# prototype_board.net
KiCad netlist of a schematic drawn in EAGLE
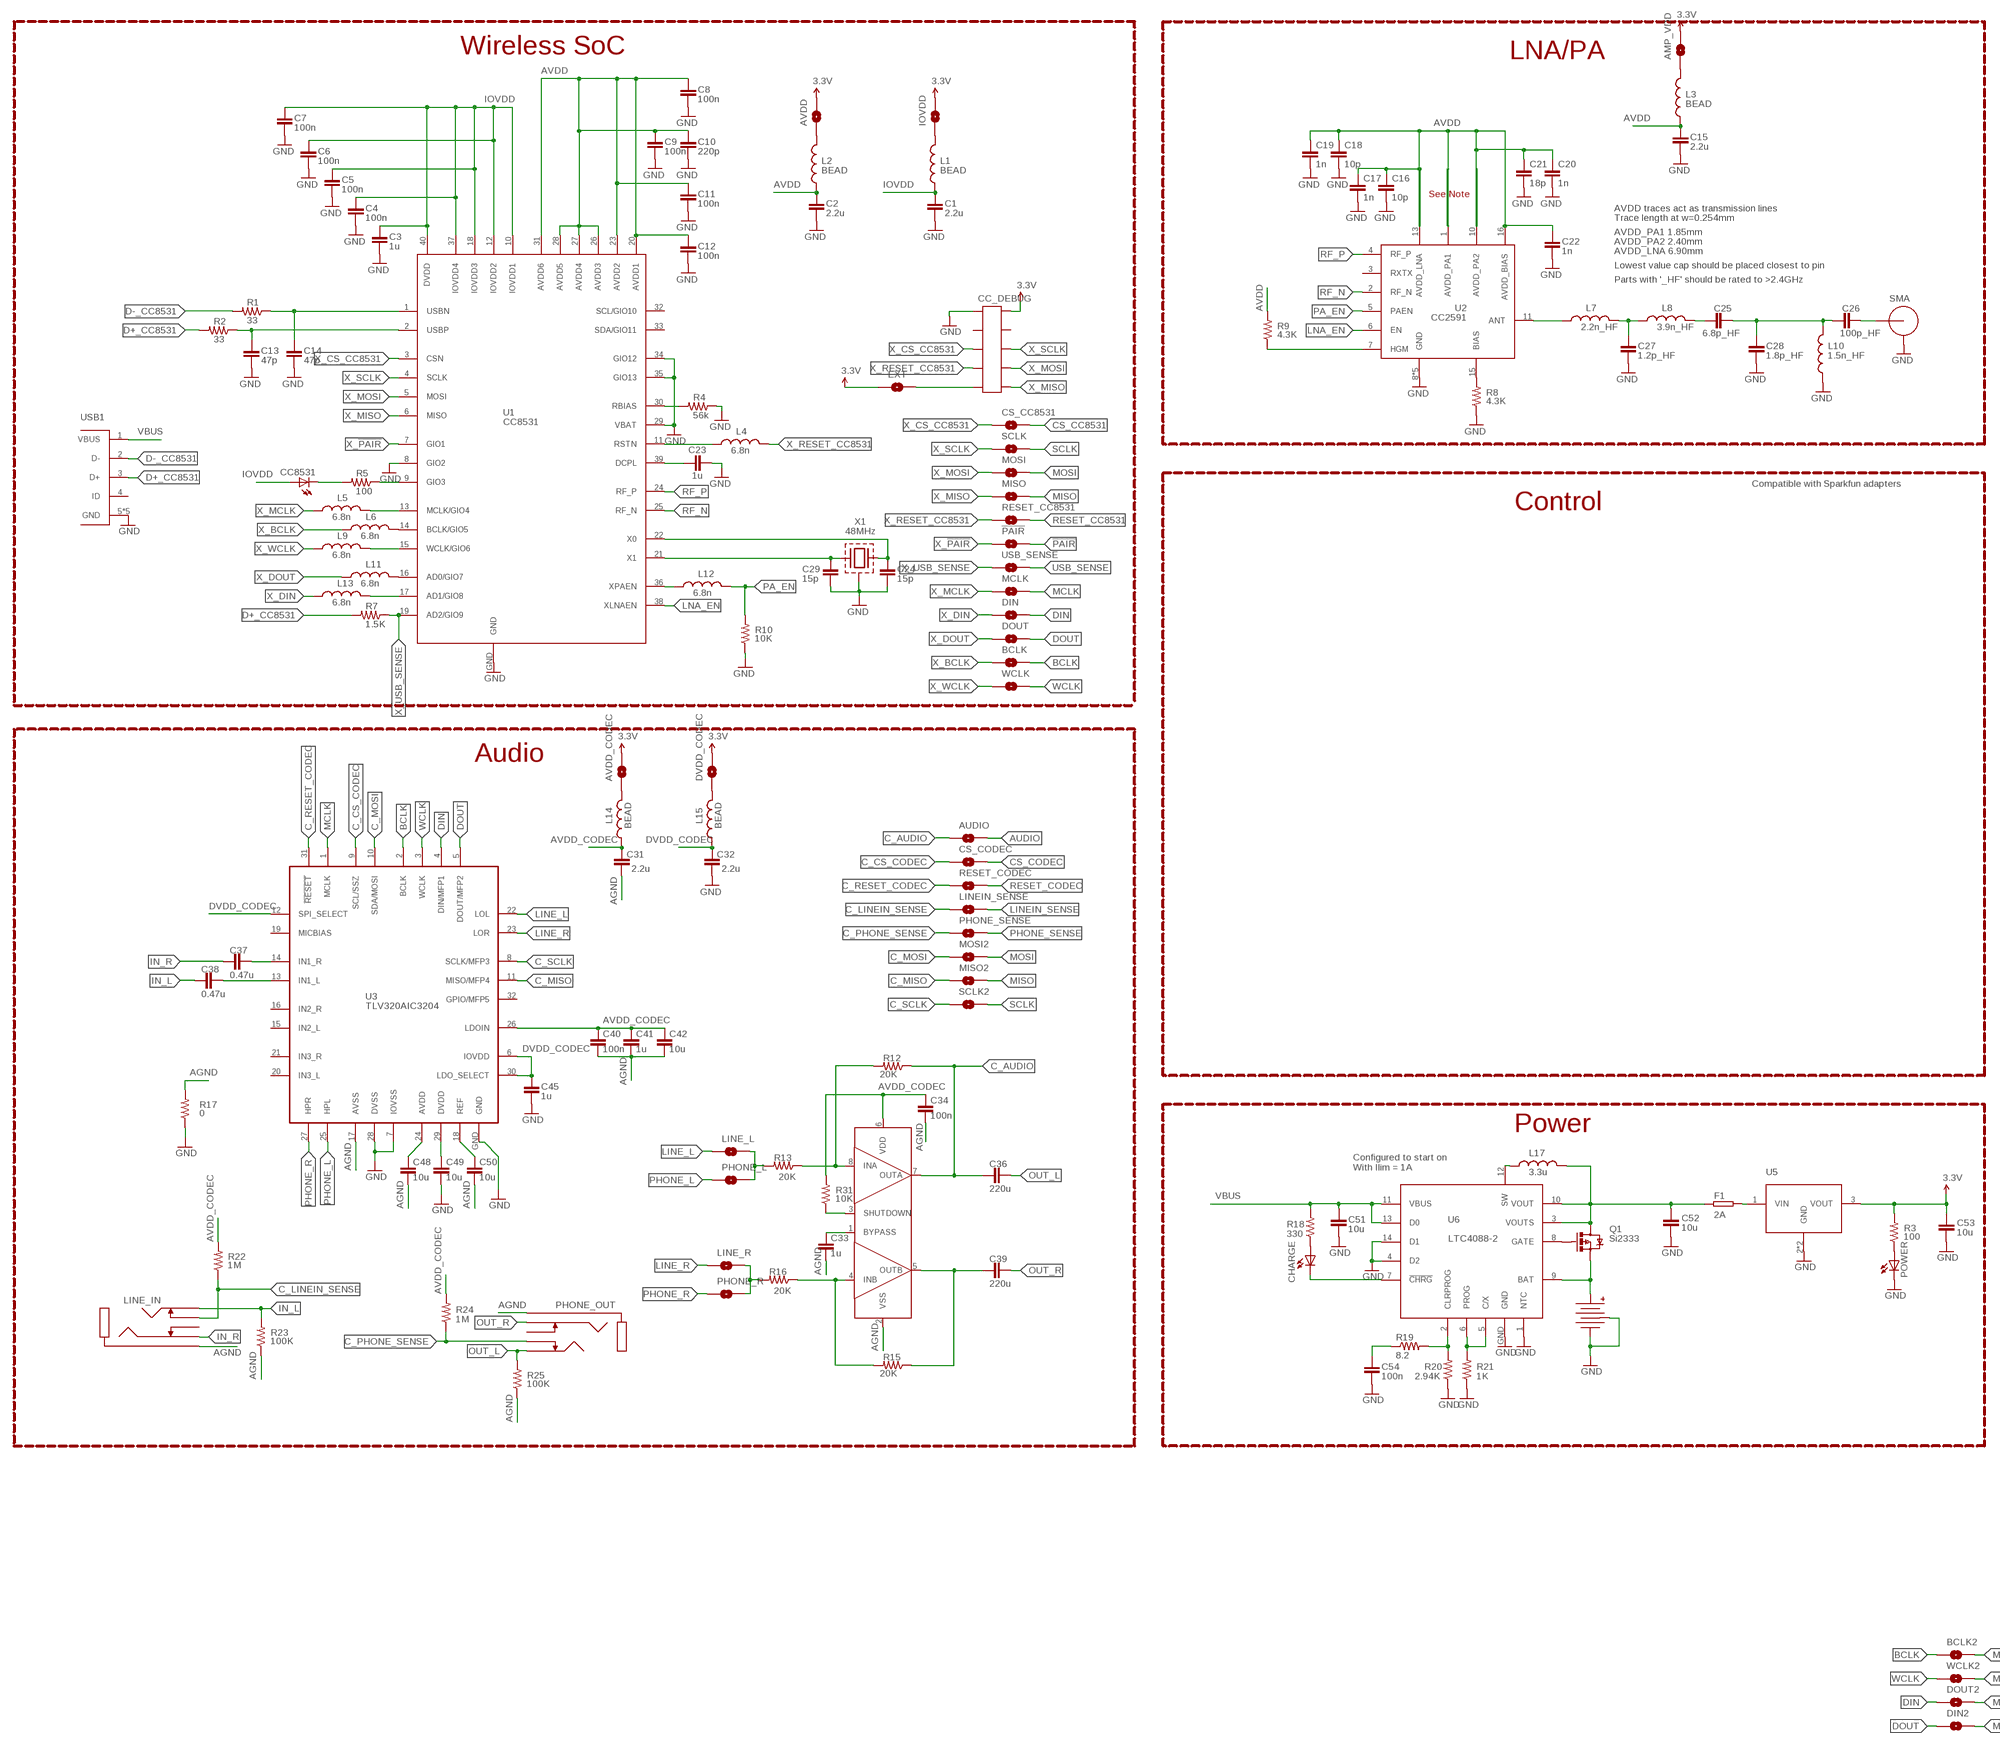
[diagram p0: schematic, sheet 1, part 1 of 3]
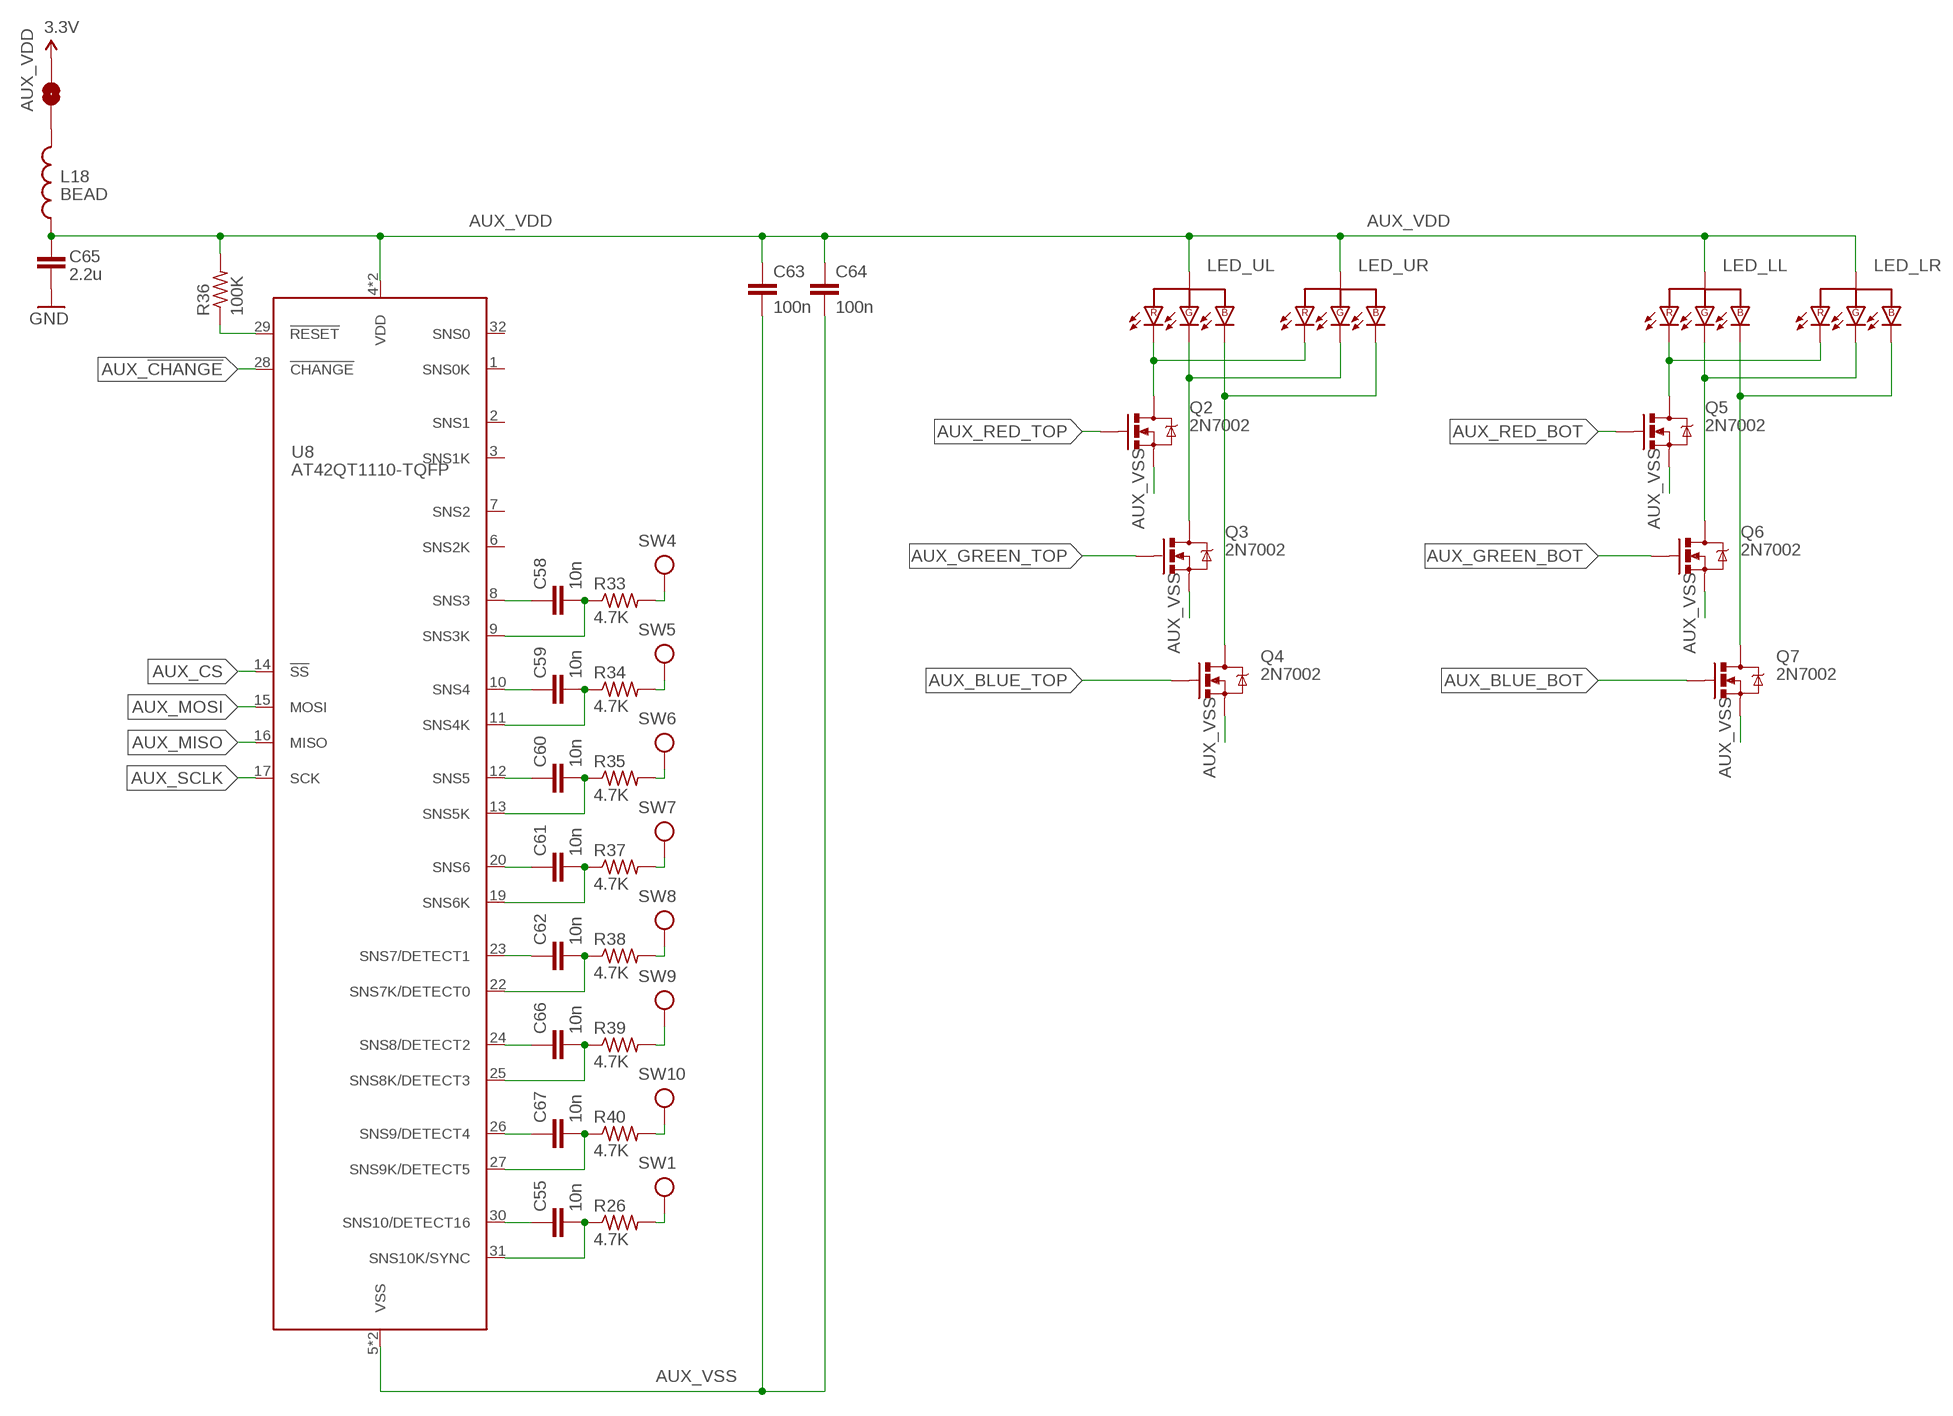
[diagram p1: schematic, sheet 1, part 2 of 3]
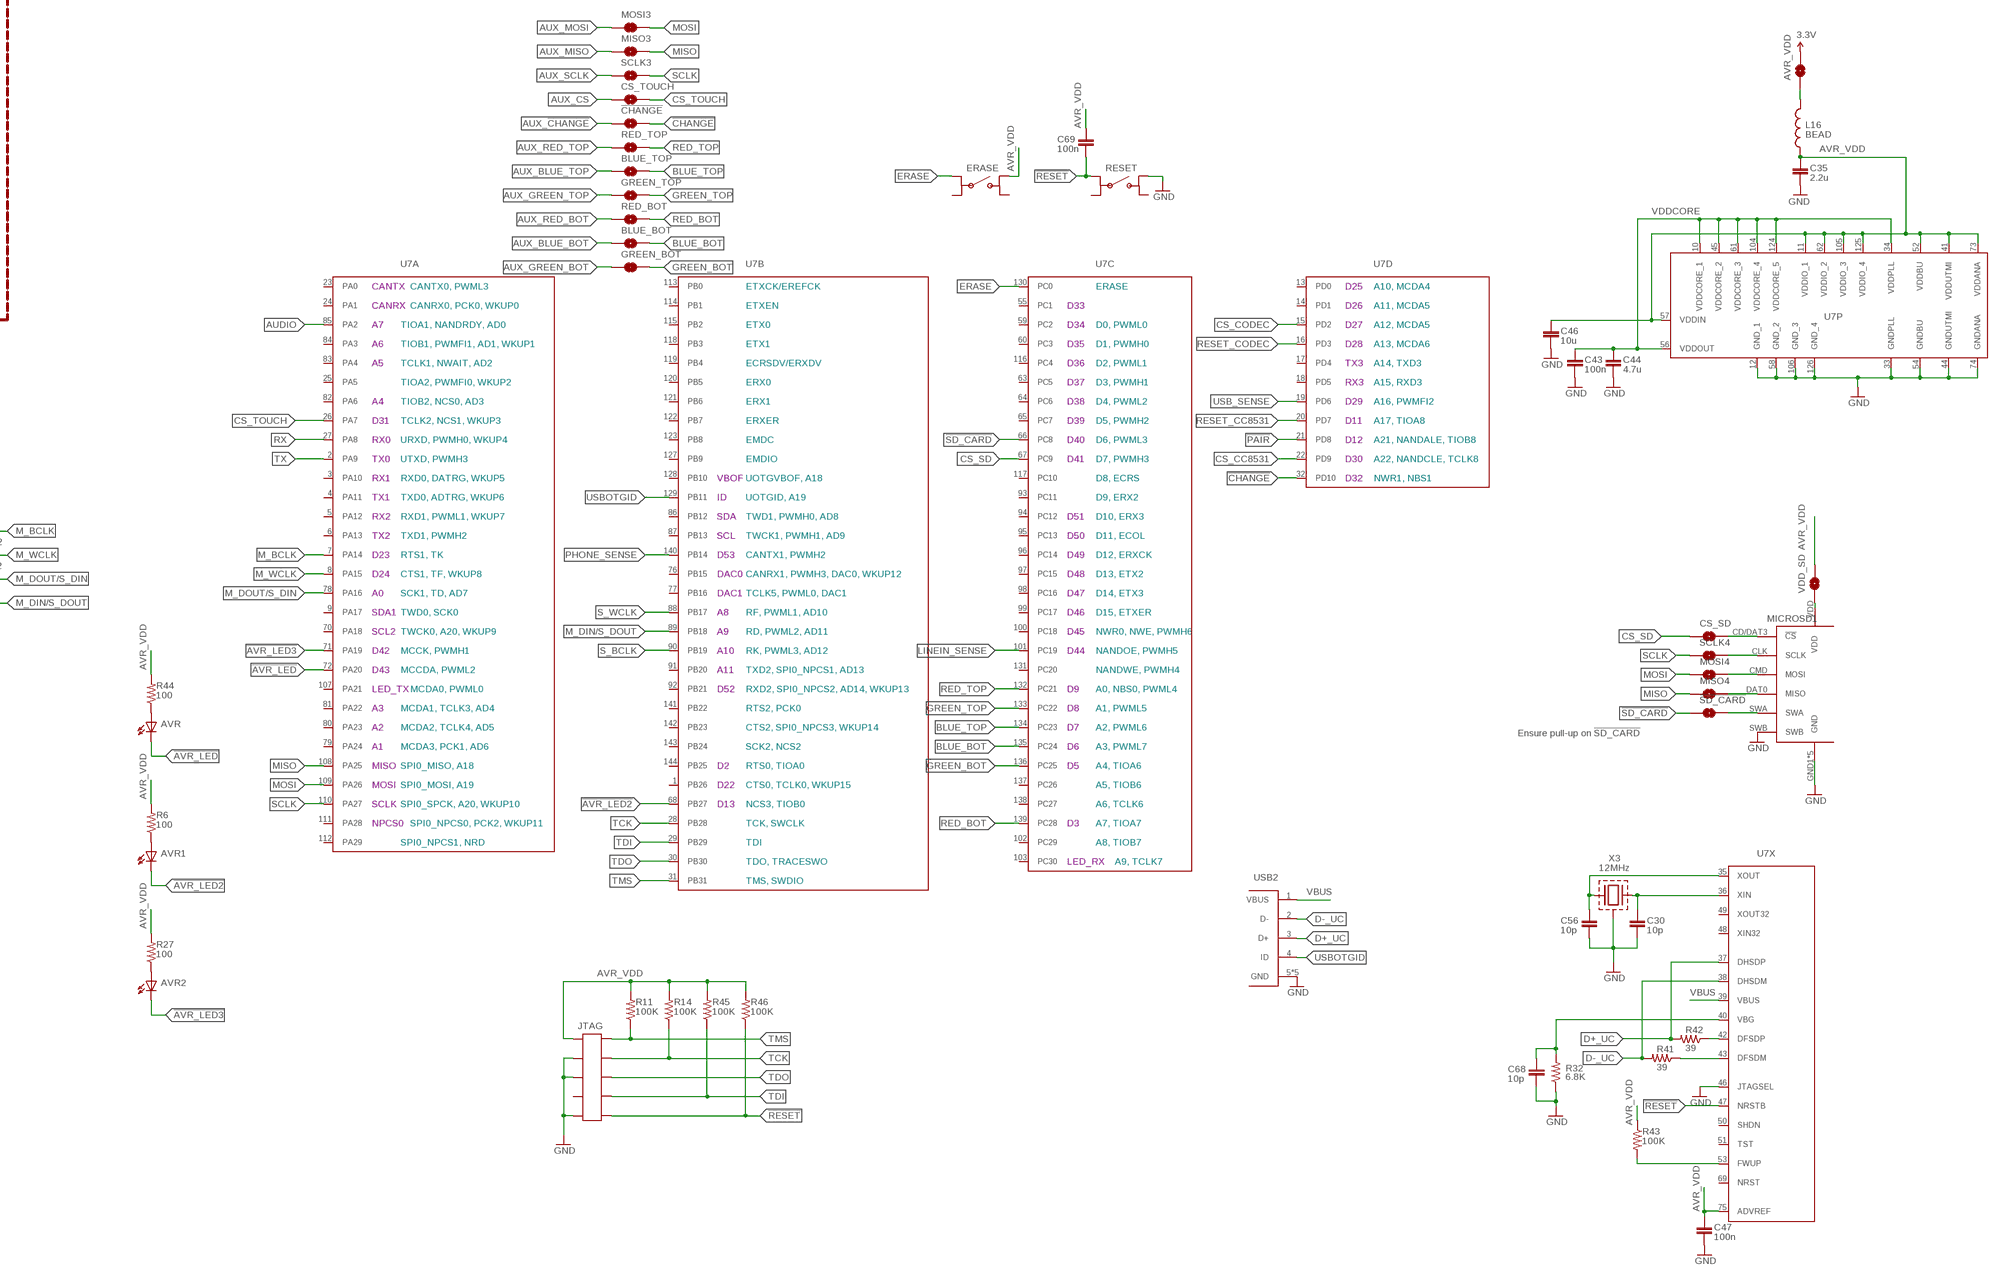
[diagram p2: schematic, sheet 1, part 3 of 3]

(export (version "E")
  (design (tool "Eeschema 10.0.6"))
  (components
    (comp (ref "!CHANGE")
      (value "SOLDERJUMPERNO")
      (footprint "eagle-import:SJ_2S-NO")
      (libsource (lib "eagle-import") (part "SOLDERJUMPERNO"))
    )
    (comp (ref "!PAIR")
      (value "SOLDERJUMPERNO")
      (footprint "eagle-import:SJ_2S-NO")
      (libsource (lib "eagle-import") (part "SOLDERJUMPERNO"))
    )
    (comp (ref "!SD_CARD")
      (value "SOLDERJUMPERNO")
      (footprint "eagle-import:SJ_2S-NO")
      (libsource (lib "eagle-import") (part "SOLDERJUMPERNO"))
    )
    (comp (ref "AMP_VDD")
      (value "SOLDERJUMPERNO")
      (footprint "eagle-import:SJ_2S-NO")
      (libsource (lib "eagle-import") (part "SOLDERJUMPERNO"))
    )
    (comp (ref "AUDIO")
      (value "SOLDERJUMPERNO")
      (footprint "eagle-import:SJ_2S-NO")
      (libsource (lib "eagle-import") (part "SOLDERJUMPERNO"))
    )
    (comp (ref "AUX_VDD")
      (value "SOLDERJUMPERNO")
      (footprint "eagle-import:SJ_2S-NO")
      (libsource (lib "eagle-import") (part "SOLDERJUMPERNO"))
    )
    (comp (ref "AVDD")
      (value "SOLDERJUMPERNO")
      (footprint "eagle-import:SJ_2S-NO")
      (libsource (lib "eagle-import") (part "SOLDERJUMPERNO"))
    )
    (comp (ref "AVDD_CODEC")
      (value "SOLDERJUMPERNO")
      (footprint "eagle-import:SJ_2S-NO")
      (libsource (lib "eagle-import") (part "SOLDERJUMPERNO"))
    )
    (comp (ref "AVR")
      (value "LED1206")
      (footprint "eagle-import:LED-1206")
      (libsource (lib "eagle-import") (part "LED1206"))
    )
    (comp (ref "AVR1")
      (value "LED1206")
      (footprint "eagle-import:LED-1206")
      (libsource (lib "eagle-import") (part "LED1206"))
    )
    (comp (ref "AVR2")
      (value "LED1206")
      (footprint "eagle-import:LED-1206")
      (libsource (lib "eagle-import") (part "LED1206"))
    )
    (comp (ref "AVR_VDD")
      (value "SOLDERJUMPERNO")
      (footprint "eagle-import:SJ_2S-NO")
      (libsource (lib "eagle-import") (part "SOLDERJUMPERNO"))
    )
    (comp (ref "BATTERY")
      (value "BATTERY-LIPO-JST")
      (footprint "eagle-import:1775469-2")
      (libsource (lib "eagle-import") (part "BATTERY-LIPO-JST"))
    )
    (comp (ref "BCLK")
      (value "SOLDERJUMPERNO")
      (footprint "eagle-import:SJ_2S-NO")
      (libsource (lib "eagle-import") (part "SOLDERJUMPERNO"))
    )
    (comp (ref "BCLK2")
      (value "SOLDERJUMPERNO")
      (footprint "eagle-import:SJ_2S-NO")
      (libsource (lib "eagle-import") (part "SOLDERJUMPERNO"))
    )
    (comp (ref "BLUE_BOT")
      (value "SOLDERJUMPERNO")
      (footprint "eagle-import:SJ_2S-NO")
      (libsource (lib "eagle-import") (part "SOLDERJUMPERNO"))
    )
    (comp (ref "BLUE_TOP")
      (value "SOLDERJUMPERNO")
      (footprint "eagle-import:SJ_2S-NO")
      (libsource (lib "eagle-import") (part "SOLDERJUMPERNO"))
    )
    (comp (ref "C1")
      (value "2.2u")
      (footprint "eagle-import:C0603")
      (libsource (lib "eagle-import") (part "rcl_C-EUC0603"))
    )
    (comp (ref "C2")
      (value "2.2u")
      (footprint "eagle-import:C0603")
      (libsource (lib "eagle-import") (part "rcl_C-EUC0603"))
    )
    (comp (ref "C3")
      (value "1u")
      (footprint "eagle-import:C0603")
      (libsource (lib "eagle-import") (part "rcl_C-EUC0603"))
    )
    (comp (ref "C4")
      (value "100n")
      (footprint "eagle-import:C0603")
      (libsource (lib "eagle-import") (part "rcl_C-EUC0603"))
    )
    (comp (ref "C5")
      (value "100n")
      (footprint "eagle-import:C0603")
      (libsource (lib "eagle-import") (part "rcl_C-EUC0603"))
    )
    (comp (ref "C6")
      (value "100n")
      (footprint "eagle-import:C0603")
      (libsource (lib "eagle-import") (part "rcl_C-EUC0603"))
    )
    (comp (ref "C7")
      (value "100n")
      (footprint "eagle-import:C0603")
      (libsource (lib "eagle-import") (part "rcl_C-EUC0603"))
    )
    (comp (ref "C8")
      (value "100n")
      (footprint "eagle-import:C0603")
      (libsource (lib "eagle-import") (part "rcl_C-EUC0603"))
    )
    (comp (ref "C9")
      (value "100n")
      (footprint "eagle-import:C0603")
      (libsource (lib "eagle-import") (part "rcl_C-EUC0603"))
    )
    (comp (ref "C10")
      (value "220p")
      (footprint "eagle-import:C0603")
      (libsource (lib "eagle-import") (part "rcl_C-EUC0603"))
    )
    (comp (ref "C11")
      (value "100n")
      (footprint "eagle-import:C0603")
      (libsource (lib "eagle-import") (part "rcl_C-EUC0603"))
    )
    (comp (ref "C12")
      (value "100n")
      (footprint "eagle-import:C0603")
      (libsource (lib "eagle-import") (part "rcl_C-EUC0603"))
    )
    (comp (ref "C13")
      (value "47p")
      (footprint "eagle-import:C0603")
      (libsource (lib "eagle-import") (part "rcl_C-EUC0603"))
    )
    (comp (ref "C14")
      (value "47p")
      (footprint "eagle-import:C0603")
      (libsource (lib "eagle-import") (part "rcl_C-EUC0603"))
    )
    (comp (ref "C15")
      (value "2.2u")
      (footprint "eagle-import:C0603")
      (libsource (lib "eagle-import") (part "rcl_C-EUC0603"))
    )
    (comp (ref "C16")
      (value "10p")
      (footprint "eagle-import:C0603")
      (libsource (lib "eagle-import") (part "rcl_C-EUC0603"))
    )
    (comp (ref "C17")
      (value "1n")
      (footprint "eagle-import:C0603")
      (libsource (lib "eagle-import") (part "rcl_C-EUC0603"))
    )
    (comp (ref "C18")
      (value "10p")
      (footprint "eagle-import:C0603")
      (libsource (lib "eagle-import") (part "rcl_C-EUC0603"))
    )
    (comp (ref "C19")
      (value "1n")
      (footprint "eagle-import:C0603")
      (libsource (lib "eagle-import") (part "rcl_C-EUC0603"))
    )
    (comp (ref "C20")
      (value "1n")
      (footprint "eagle-import:C0603")
      (libsource (lib "eagle-import") (part "rcl_C-EUC0603"))
    )
    (comp (ref "C21")
      (value "18p")
      (footprint "eagle-import:C0603")
      (libsource (lib "eagle-import") (part "rcl_C-EUC0603"))
    )
    (comp (ref "C22")
      (value "1n")
      (footprint "eagle-import:C0603")
      (libsource (lib "eagle-import") (part "rcl_C-EUC0603"))
    )
    (comp (ref "C23")
      (value "1u")
      (footprint "eagle-import:C0603")
      (libsource (lib "eagle-import") (part "rcl_C-EUC0603"))
    )
    (comp (ref "C24")
      (value "15p")
      (footprint "eagle-import:C0603")
      (libsource (lib "eagle-import") (part "rcl_C-EUC0603"))
    )
    (comp (ref "C25")
      (value "6.8p_HF")
      (footprint "eagle-import:C0603")
      (libsource (lib "eagle-import") (part "rcl_C-EUC0603"))
    )
    (comp (ref "C26")
      (value "100p_HF")
      (footprint "eagle-import:C0603")
      (libsource (lib "eagle-import") (part "rcl_C-EUC0603"))
    )
    (comp (ref "C27")
      (value "1.2p_HF")
      (footprint "eagle-import:C0603")
      (libsource (lib "eagle-import") (part "rcl_C-EUC0603"))
    )
    (comp (ref "C28")
      (value "1.8p_HF")
      (footprint "eagle-import:C0603")
      (libsource (lib "eagle-import") (part "rcl_C-EUC0603"))
    )
    (comp (ref "C29")
      (value "15p")
      (footprint "eagle-import:C0603")
      (libsource (lib "eagle-import") (part "rcl_C-EUC0603"))
    )
    (comp (ref "C30")
      (value "10p")
      (footprint "eagle-import:C0603")
      (libsource (lib "eagle-import") (part "C-EUC0603"))
    )
    (comp (ref "C31")
      (value "2.2u")
      (footprint "eagle-import:C0603")
      (libsource (lib "eagle-import") (part "rcl_C-EUC0603"))
    )
    (comp (ref "C32")
      (value "2.2u")
      (footprint "eagle-import:C0603")
      (libsource (lib "eagle-import") (part "rcl_C-EUC0603"))
    )
    (comp (ref "C33")
      (value "1u")
      (footprint "eagle-import:C0603")
      (libsource (lib "eagle-import") (part "rcl_C-EUC0603"))
    )
    (comp (ref "C34")
      (value "100n")
      (footprint "eagle-import:C0603")
      (libsource (lib "eagle-import") (part "rcl_C-EUC0603"))
    )
    (comp (ref "C35")
      (value "2.2u")
      (footprint "eagle-import:C0603")
      (libsource (lib "eagle-import") (part "rcl_C-EUC0603"))
    )
    (comp (ref "C36")
      (value "220u")
      (footprint "eagle-import:C1210")
      (libsource (lib "eagle-import") (part "C-EUC1210"))
    )
    (comp (ref "C37")
      (value "0.47u")
      (footprint "eagle-import:C0603")
      (libsource (lib "eagle-import") (part "rcl_C-EUC0603"))
    )
    (comp (ref "C38")
      (value "0.47u")
      (footprint "eagle-import:C0603")
      (libsource (lib "eagle-import") (part "rcl_C-EUC0603"))
    )
    (comp (ref "C39")
      (value "220u")
      (footprint "eagle-import:C1210")
      (libsource (lib "eagle-import") (part "C-EUC1210"))
    )
    (comp (ref "C40")
      (value "100n")
      (footprint "eagle-import:C0603")
      (libsource (lib "eagle-import") (part "rcl_C-EUC0603"))
    )
    (comp (ref "C41")
      (value "1u")
      (footprint "eagle-import:C0603")
      (libsource (lib "eagle-import") (part "rcl_C-EUC0603"))
    )
    (comp (ref "C42")
      (value "10u")
      (footprint "eagle-import:C0603")
      (libsource (lib "eagle-import") (part "rcl_C-EUC0603"))
    )
    (comp (ref "C43")
      (value "100n")
      (footprint "eagle-import:C0603")
      (libsource (lib "eagle-import") (part "rcl_C-EUC0603"))
    )
    (comp (ref "C44")
      (value "4.7u")
      (footprint "eagle-import:C0603")
      (libsource (lib "eagle-import") (part "rcl_C-EUC0603"))
    )
    (comp (ref "C45")
      (value "1u")
      (footprint "eagle-import:C0603")
      (libsource (lib "eagle-import") (part "rcl_C-EUC0603"))
    )
    (comp (ref "C46")
      (value "10u")
      (footprint "eagle-import:C0603")
      (libsource (lib "eagle-import") (part "rcl_C-EUC0603"))
    )
    (comp (ref "C47")
      (value "100n")
      (footprint "eagle-import:C0603")
      (libsource (lib "eagle-import") (part "rcl_C-EUC0603"))
    )
    (comp (ref "C48")
      (value "10u")
      (footprint "eagle-import:C0603")
      (libsource (lib "eagle-import") (part "rcl_C-EUC0603"))
    )
    (comp (ref "C49")
      (value "10u")
      (footprint "eagle-import:C0603")
      (libsource (lib "eagle-import") (part "rcl_C-EUC0603"))
    )
    (comp (ref "C50")
      (value "10u")
      (footprint "eagle-import:C0603")
      (libsource (lib "eagle-import") (part "rcl_C-EUC0603"))
    )
    (comp (ref "C51")
      (value "10u")
      (footprint "eagle-import:C0603")
      (libsource (lib "eagle-import") (part "C-EUC0603"))
    )
    (comp (ref "C52")
      (value "10u")
      (footprint "eagle-import:C0603")
      (libsource (lib "eagle-import") (part "rcl_C-EUC0603"))
    )
    (comp (ref "C53")
      (value "10u")
      (footprint "eagle-import:C0603")
      (libsource (lib "eagle-import") (part "rcl_C-EUC0603"))
    )
    (comp (ref "C54")
      (value "100n")
      (footprint "eagle-import:C0603")
      (libsource (lib "eagle-import") (part "C-EUC0603"))
    )
    (comp (ref "C55")
      (value "10n")
      (footprint "eagle-import:C0603")
      (libsource (lib "eagle-import") (part "rcl_C-EUC0603"))
    )
    (comp (ref "C56")
      (value "10p")
      (footprint "eagle-import:C0603")
      (libsource (lib "eagle-import") (part "C-EUC0603"))
    )
    (comp (ref "C58")
      (value "10n")
      (footprint "eagle-import:C0603")
      (libsource (lib "eagle-import") (part "rcl_C-EUC0603"))
    )
    (comp (ref "C59")
      (value "10n")
      (footprint "eagle-import:C0603")
      (libsource (lib "eagle-import") (part "rcl_C-EUC0603"))
    )
    (comp (ref "C60")
      (value "10n")
      (footprint "eagle-import:C0603")
      (libsource (lib "eagle-import") (part "rcl_C-EUC0603"))
    )
    (comp (ref "C61")
      (value "10n")
      (footprint "eagle-import:C0603")
      (libsource (lib "eagle-import") (part "rcl_C-EUC0603"))
    )
    (comp (ref "C62")
      (value "10n")
      (footprint "eagle-import:C0603")
      (libsource (lib "eagle-import") (part "rcl_C-EUC0603"))
    )
    (comp (ref "C63")
      (value "100n")
      (footprint "eagle-import:C0603")
      (libsource (lib "eagle-import") (part "rcl_C-EUC0603"))
    )
    (comp (ref "C64")
      (value "100n")
      (footprint "eagle-import:C0603")
      (libsource (lib "eagle-import") (part "rcl_C-EUC0603"))
    )
    (comp (ref "C65")
      (value "2.2u")
      (footprint "eagle-import:C0603")
      (libsource (lib "eagle-import") (part "rcl_C-EUC0603"))
    )
    (comp (ref "C66")
      (value "10n")
      (footprint "eagle-import:C0603")
      (libsource (lib "eagle-import") (part "rcl_C-EUC0603"))
    )
    (comp (ref "C67")
      (value "10n")
      (footprint "eagle-import:C0603")
      (libsource (lib "eagle-import") (part "rcl_C-EUC0603"))
    )
    (comp (ref "C68")
      (value "10p")
      (footprint "eagle-import:C0603")
      (libsource (lib "eagle-import") (part "C-EUC0603"))
    )
    (comp (ref "C69")
      (value "100n")
      (footprint "eagle-import:C0603")
      (libsource (lib "eagle-import") (part "C-EUC0603"))
    )
    (comp (ref "CC8531")
      (value "LED1206")
      (footprint "eagle-import:LED-1206")
      (libsource (lib "eagle-import") (part "LED1206"))
    )
    (comp (ref "CC_DEBUG")
      (value "HEADER-10P-SMD-MALE2")
      (footprint "eagle-import:HEADER-10P-1.27MM")
      (libsource (lib "eagle-import") (part "HEADER-10P-SMD-MALE2"))
    )
    (comp (ref "CHARGE")
      (value "LED1206")
      (footprint "eagle-import:LED-1206")
      (libsource (lib "eagle-import") (part "LED1206"))
    )
    (comp (ref "CS_CC8531")
      (value "SOLDERJUMPERNO")
      (footprint "eagle-import:SJ_2S-NO")
      (libsource (lib "eagle-import") (part "SOLDERJUMPERNO"))
    )
    (comp (ref "CS_CODEC")
      (value "SOLDERJUMPERNO")
      (footprint "eagle-import:SJ_2S-NO")
      (libsource (lib "eagle-import") (part "SOLDERJUMPERNO"))
    )
    (comp (ref "CS_SD")
      (value "SOLDERJUMPERNO")
      (footprint "eagle-import:SJ_2S-NO")
      (libsource (lib "eagle-import") (part "SOLDERJUMPERNO"))
    )
    (comp (ref "CS_TOUCH")
      (value "SOLDERJUMPERNO")
      (footprint "eagle-import:SJ_2S-NO")
      (libsource (lib "eagle-import") (part "SOLDERJUMPERNO"))
    )
    (comp (ref "DIN")
      (value "SOLDERJUMPERNO")
      (footprint "eagle-import:SJ_2S-NO")
      (libsource (lib "eagle-import") (part "SOLDERJUMPERNO"))
    )
    (comp (ref "DIN2")
      (value "SOLDERJUMPERNO")
      (footprint "eagle-import:SJ_2S-NO")
      (libsource (lib "eagle-import") (part "SOLDERJUMPERNO"))
    )
    (comp (ref "DOUT")
      (value "SOLDERJUMPERNO")
      (footprint "eagle-import:SJ_2S-NO")
      (libsource (lib "eagle-import") (part "SOLDERJUMPERNO"))
    )
    (comp (ref "DOUT2")
      (value "SOLDERJUMPERNO")
      (footprint "eagle-import:SJ_2S-NO")
      (libsource (lib "eagle-import") (part "SOLDERJUMPERNO"))
    )
    (comp (ref "DVDD_CODEC")
      (value "SOLDERJUMPERNO")
      (footprint "eagle-import:SJ_2S-NO")
      (libsource (lib "eagle-import") (part "SOLDERJUMPERNO"))
    )
    (comp (ref "ERASE")
      (value "TACT_SWITCH-PTS-525")
      (footprint "eagle-import:PTS-525")
      (libsource (lib "eagle-import") (part "TACT_SWITCH-PTS-525"))
    )
    (comp (ref "EXT")
      (value "SOLDERJUMPERNO")
      (footprint "eagle-import:SJ_2S-NO")
      (libsource (lib "eagle-import") (part "SOLDERJUMPERNO"))
    )
    (comp (ref "F1")
      (value "2A")
      (footprint "eagle-import:1210")
      (libsource (lib "eagle-import") (part "PTC_FUSE"))
    )
    (comp (ref "GREEN_BOT")
      (value "SOLDERJUMPERNO")
      (footprint "eagle-import:SJ_2S-NO")
      (libsource (lib "eagle-import") (part "SOLDERJUMPERNO"))
    )
    (comp (ref "GREEN_TOP")
      (value "SOLDERJUMPERNO")
      (footprint "eagle-import:SJ_2S-NO")
      (libsource (lib "eagle-import") (part "SOLDERJUMPERNO"))
    )
    (comp (ref "IOVDD")
      (value "SOLDERJUMPERNO")
      (footprint "eagle-import:SJ_2S-NO")
      (libsource (lib "eagle-import") (part "SOLDERJUMPERNO"))
    )
    (comp (ref "JTAG")
      (value "HEADER-10P-SMD-MALE2")
      (footprint "eagle-import:HEADER-10P-1.27MM")
      (libsource (lib "eagle-import") (part "HEADER-10P-SMD-MALE2"))
    )
    (comp (ref "L1")
      (value "BEAD")
      (footprint "eagle-import:0603")
      (libsource (lib "eagle-import") (part "INDUCTOR0603"))
    )
    (comp (ref "L2")
      (value "BEAD")
      (footprint "eagle-import:0603")
      (libsource (lib "eagle-import") (part "INDUCTOR0603"))
    )
    (comp (ref "L3")
      (value "BEAD")
      (footprint "eagle-import:0603")
      (libsource (lib "eagle-import") (part "INDUCTOR0603"))
    )
    (comp (ref "L4")
      (value "6.8n")
      (footprint "eagle-import:0603")
      (libsource (lib "eagle-import") (part "INDUCTOR0603"))
    )
    (comp (ref "L5")
      (value "6.8n")
      (footprint "eagle-import:0603")
      (libsource (lib "eagle-import") (part "INDUCTOR0603"))
    )
    (comp (ref "L6")
      (value "6.8n")
      (footprint "eagle-import:0603")
      (libsource (lib "eagle-import") (part "INDUCTOR0603"))
    )
    (comp (ref "L7")
      (value "2.2n_HF")
      (footprint "eagle-import:0603")
      (libsource (lib "eagle-import") (part "INDUCTOR0603"))
    )
    (comp (ref "L8")
      (value "3.9n_HF")
      (footprint "eagle-import:0603")
      (libsource (lib "eagle-import") (part "INDUCTOR0603"))
    )
    (comp (ref "L9")
      (value "6.8n")
      (footprint "eagle-import:0603")
      (libsource (lib "eagle-import") (part "INDUCTOR0603"))
    )
    (comp (ref "L10")
      (value "1.5n_HF")
      (footprint "eagle-import:0603")
      (libsource (lib "eagle-import") (part "INDUCTOR0603"))
    )
    (comp (ref "L11")
      (value "6.8n")
      (footprint "eagle-import:0603")
      (libsource (lib "eagle-import") (part "INDUCTOR0603"))
    )
    (comp (ref "L12")
      (value "6.8n")
      (footprint "eagle-import:0603")
      (libsource (lib "eagle-import") (part "INDUCTOR0603"))
    )
    (comp (ref "L13")
      (value "6.8n")
      (footprint "eagle-import:0603")
      (libsource (lib "eagle-import") (part "INDUCTOR0603"))
    )
    (comp (ref "L14")
      (value "BEAD")
      (footprint "eagle-import:0603")
      (libsource (lib "eagle-import") (part "INDUCTOR0603"))
    )
    (comp (ref "L15")
      (value "BEAD")
      (footprint "eagle-import:0603")
      (libsource (lib "eagle-import") (part "INDUCTOR0603"))
    )
    (comp (ref "L16")
      (value "BEAD")
      (footprint "eagle-import:0603")
      (libsource (lib "eagle-import") (part "INDUCTOR0603"))
    )
    (comp (ref "L17")
      (value "3.3u")
      (footprint "eagle-import:IFSC-1111AB-01")
      (libsource (lib "eagle-import") (part "IFSC-1111AB-01"))
    )
    (comp (ref "L18")
      (value "BEAD")
      (footprint "eagle-import:0603")
      (libsource (lib "eagle-import") (part "INDUCTOR0603"))
    )
    (comp (ref "LED_LL")
      (value "LED_RGB")
      (footprint "eagle-import:PLCC-4")
      (libsource (lib "eagle-import") (part "LED_RGB"))
    )
    (comp (ref "LED_LR")
      (value "LED_RGB")
      (footprint "eagle-import:PLCC-4")
      (libsource (lib "eagle-import") (part "LED_RGB"))
    )
    (comp (ref "LED_UL")
      (value "LED_RGB")
      (footprint "eagle-import:PLCC-4")
      (libsource (lib "eagle-import") (part "LED_RGB"))
    )
    (comp (ref "LED_UR")
      (value "LED_RGB")
      (footprint "eagle-import:PLCC-4")
      (libsource (lib "eagle-import") (part "LED_RGB"))
    )
    (comp (ref "LINEIN_SENSE")
      (value "SOLDERJUMPERNO")
      (footprint "eagle-import:SJ_2S-NO")
      (libsource (lib "eagle-import") (part "SOLDERJUMPERNO"))
    )
    (comp (ref "LINE_IN")
      (value "PHONE_SW-STX-35332-5N")
      (footprint "eagle-import:STX-35332-5N")
      (libsource (lib "eagle-import") (part "PHONE_SW-STX-35332-5N"))
    )
    (comp (ref "LINE_L")
      (value "SOLDERJUMPERNO")
      (footprint "eagle-import:SJ_2S-NO")
      (libsource (lib "eagle-import") (part "SOLDERJUMPERNO"))
    )
    (comp (ref "LINE_R")
      (value "SOLDERJUMPERNO")
      (footprint "eagle-import:SJ_2S-NO")
      (libsource (lib "eagle-import") (part "SOLDERJUMPERNO"))
    )
    (comp (ref "MCLK")
      (value "SOLDERJUMPERNO")
      (footprint "eagle-import:SJ_2S-NO")
      (libsource (lib "eagle-import") (part "SOLDERJUMPERNO"))
    )
    (comp (ref "MICROSD1")
      (value "MICROSD104031-0811")
      (footprint "eagle-import:MOLEX_104031-0811")
      (libsource (lib "eagle-import") (part "MICROSD104031-0811"))
    )
    (comp (ref "MISO")
      (value "SOLDERJUMPERNO")
      (footprint "eagle-import:SJ_2S-NO")
      (libsource (lib "eagle-import") (part "SOLDERJUMPERNO"))
    )
    (comp (ref "MISO2")
      (value "SOLDERJUMPERNO")
      (footprint "eagle-import:SJ_2S-NO")
      (libsource (lib "eagle-import") (part "SOLDERJUMPERNO"))
    )
    (comp (ref "MISO3")
      (value "SOLDERJUMPERNO")
      (footprint "eagle-import:SJ_2S-NO")
      (libsource (lib "eagle-import") (part "SOLDERJUMPERNO"))
    )
    (comp (ref "MISO4")
      (value "SOLDERJUMPERNO")
      (footprint "eagle-import:SJ_2S-NO")
      (libsource (lib "eagle-import") (part "SOLDERJUMPERNO"))
    )
    (comp (ref "MOSI")
      (value "SOLDERJUMPERNO")
      (footprint "eagle-import:SJ_2S-NO")
      (libsource (lib "eagle-import") (part "SOLDERJUMPERNO"))
    )
    (comp (ref "MOSI2")
      (value "SOLDERJUMPERNO")
      (footprint "eagle-import:SJ_2S-NO")
      (libsource (lib "eagle-import") (part "SOLDERJUMPERNO"))
    )
    (comp (ref "MOSI3")
      (value "SOLDERJUMPERNO")
      (footprint "eagle-import:SJ_2S-NO")
      (libsource (lib "eagle-import") (part "SOLDERJUMPERNO"))
    )
    (comp (ref "MOSI4")
      (value "SOLDERJUMPERNO")
      (footprint "eagle-import:SJ_2S-NO")
      (libsource (lib "eagle-import") (part "SOLDERJUMPERNO"))
    )
    (comp (ref "PHONE_L")
      (value "SOLDERJUMPERNO")
      (footprint "eagle-import:SJ_2S-NO")
      (libsource (lib "eagle-import") (part "SOLDERJUMPERNO"))
    )
    (comp (ref "PHONE_OUT")
      (value "PHONE_SW-STX-35332-5N")
      (footprint "eagle-import:STX-35332-5N")
      (libsource (lib "eagle-import") (part "PHONE_SW-STX-35332-5N"))
    )
    (comp (ref "PHONE_R")
      (value "SOLDERJUMPERNO")
      (footprint "eagle-import:SJ_2S-NO")
      (libsource (lib "eagle-import") (part "SOLDERJUMPERNO"))
    )
    (comp (ref "PHONE_SENSE")
      (value "SOLDERJUMPERNO")
      (footprint "eagle-import:SJ_2S-NO")
      (libsource (lib "eagle-import") (part "SOLDERJUMPERNO"))
    )
    (comp (ref "POWER")
      (value "LED1206")
      (footprint "eagle-import:LED-1206")
      (libsource (lib "eagle-import") (part "LED1206"))
    )
    (comp (ref "Q1")
      (value "Si2333")
      (footprint "eagle-import:SOT23-3")
      (libsource (lib "eagle-import") (part "MOSFET-PCHANNELSMD"))
    )
    (comp (ref "Q2")
      (value "2N7002")
      (footprint "eagle-import:SOT23-3")
      (libsource (lib "eagle-import") (part "MOSFET-NCHANNELSMD"))
    )
    (comp (ref "Q3")
      (value "2N7002")
      (footprint "eagle-import:SOT23-3")
      (libsource (lib "eagle-import") (part "MOSFET-NCHANNELSMD"))
    )
    (comp (ref "Q4")
      (value "2N7002")
      (footprint "eagle-import:SOT23-3")
      (libsource (lib "eagle-import") (part "MOSFET-NCHANNELSMD"))
    )
    (comp (ref "Q5")
      (value "2N7002")
      (footprint "eagle-import:SOT23-3")
      (libsource (lib "eagle-import") (part "MOSFET-NCHANNELSMD"))
    )
    (comp (ref "Q6")
      (value "2N7002")
      (footprint "eagle-import:SOT23-3")
      (libsource (lib "eagle-import") (part "MOSFET-NCHANNELSMD"))
    )
    (comp (ref "Q7")
      (value "2N7002")
      (footprint "eagle-import:SOT23-3")
      (libsource (lib "eagle-import") (part "MOSFET-NCHANNELSMD"))
    )
    (comp (ref "R1")
      (value "33")
      (footprint "eagle-import:R0603")
      (libsource (lib "eagle-import") (part "rcl_R-US_R0603"))
    )
    (comp (ref "R2")
      (value "33")
      (footprint "eagle-import:R0603")
      (libsource (lib "eagle-import") (part "rcl_R-US_R0603"))
    )
    (comp (ref "R3")
      (value "100")
      (footprint "eagle-import:R0603")
      (libsource (lib "eagle-import") (part "rcl_R-US_R0603"))
    )
    (comp (ref "R4")
      (value "56k")
      (footprint "eagle-import:R0603")
      (libsource (lib "eagle-import") (part "rcl_R-US_R0603"))
    )
    (comp (ref "R5")
      (value "100")
      (footprint "eagle-import:R0603")
      (libsource (lib "eagle-import") (part "rcl_R-US_R0603"))
    )
    (comp (ref "R6")
      (value "100")
      (footprint "eagle-import:R0603")
      (libsource (lib "eagle-import") (part "rcl_R-US_R0603"))
    )
    (comp (ref "R7")
      (value "1.5K")
      (footprint "eagle-import:R0603")
      (libsource (lib "eagle-import") (part "rcl_R-US_R0603"))
    )
    (comp (ref "R8")
      (value "4.3K")
      (footprint "eagle-import:R0603")
      (libsource (lib "eagle-import") (part "rcl_R-US_R0603"))
    )
    (comp (ref "R9")
      (value "4.3K")
      (footprint "eagle-import:R0603")
      (libsource (lib "eagle-import") (part "rcl_R-US_R0603"))
    )
    (comp (ref "R10")
      (value "10K")
      (footprint "eagle-import:R0603")
      (libsource (lib "eagle-import") (part "rcl_R-US_R0603"))
    )
    (comp (ref "R11")
      (value "100K")
      (footprint "eagle-import:R0603")
      (libsource (lib "eagle-import") (part "rcl_R-US_R0603"))
    )
    (comp (ref "R12")
      (value "20K")
      (footprint "eagle-import:R0603")
      (libsource (lib "eagle-import") (part "R-US_R0603"))
    )
    (comp (ref "R13")
      (value "20K")
      (footprint "eagle-import:R0603")
      (libsource (lib "eagle-import") (part "R-US_R0603"))
    )
    (comp (ref "R14")
      (value "100K")
      (footprint "eagle-import:R0603")
      (libsource (lib "eagle-import") (part "rcl_R-US_R0603"))
    )
    (comp (ref "R15")
      (value "20K")
      (footprint "eagle-import:R0603")
      (libsource (lib "eagle-import") (part "R-US_R0603"))
    )
    (comp (ref "R16")
      (value "20K")
      (footprint "eagle-import:R0603")
      (libsource (lib "eagle-import") (part "R-US_R0603"))
    )
    (comp (ref "R17")
      (value "0")
      (footprint "eagle-import:R0603")
      (libsource (lib "eagle-import") (part "rcl_R-US_R0603"))
    )
    (comp (ref "R18")
      (value "330")
      (footprint "eagle-import:R0603")
      (libsource (lib "eagle-import") (part "R-US_R0603"))
    )
    (comp (ref "R19")
      (value "8.2")
      (footprint "eagle-import:R0603")
      (libsource (lib "eagle-import") (part "R-US_R0603"))
    )
    (comp (ref "R20")
      (value "2.94K")
      (footprint "eagle-import:R0603")
      (libsource (lib "eagle-import") (part "R-US_R0603"))
    )
    (comp (ref "R21")
      (value "1K")
      (footprint "eagle-import:R0603")
      (libsource (lib "eagle-import") (part "R-US_R0603"))
    )
    (comp (ref "R22")
      (value "1M")
      (footprint "eagle-import:R0603")
      (libsource (lib "eagle-import") (part "rcl_R-US_R0603"))
    )
    (comp (ref "R23")
      (value "100K")
      (footprint "eagle-import:R0603")
      (libsource (lib "eagle-import") (part "rcl_R-US_R0603"))
    )
    (comp (ref "R24")
      (value "1M")
      (footprint "eagle-import:R0603")
      (libsource (lib "eagle-import") (part "rcl_R-US_R0603"))
    )
    (comp (ref "R25")
      (value "100K")
      (footprint "eagle-import:R0603")
      (libsource (lib "eagle-import") (part "rcl_R-US_R0603"))
    )
    (comp (ref "R26")
      (value "4.7K")
      (footprint "eagle-import:R0603")
      (libsource (lib "eagle-import") (part "rcl_R-US_R0603"))
    )
    (comp (ref "R27")
      (value "100")
      (footprint "eagle-import:R0603")
      (libsource (lib "eagle-import") (part "rcl_R-US_R0603"))
    )
    (comp (ref "R31")
      (value "10K")
      (footprint "eagle-import:R0603")
      (libsource (lib "eagle-import") (part "rcl_R-US_R0603"))
    )
    (comp (ref "R32")
      (value "6.8K")
      (footprint "eagle-import:R0603")
      (libsource (lib "eagle-import") (part "rcl_R-US_R0603"))
    )
    (comp (ref "R33")
      (value "4.7K")
      (footprint "eagle-import:R0603")
      (libsource (lib "eagle-import") (part "rcl_R-US_R0603"))
    )
    (comp (ref "R34")
      (value "4.7K")
      (footprint "eagle-import:R0603")
      (libsource (lib "eagle-import") (part "rcl_R-US_R0603"))
    )
    (comp (ref "R35")
      (value "4.7K")
      (footprint "eagle-import:R0603")
      (libsource (lib "eagle-import") (part "rcl_R-US_R0603"))
    )
    (comp (ref "R36")
      (value "100K")
      (footprint "eagle-import:R0603")
      (libsource (lib "eagle-import") (part "rcl_R-US_R0603"))
    )
    (comp (ref "R37")
      (value "4.7K")
      (footprint "eagle-import:R0603")
      (libsource (lib "eagle-import") (part "rcl_R-US_R0603"))
    )
    (comp (ref "R38")
      (value "4.7K")
      (footprint "eagle-import:R0603")
      (libsource (lib "eagle-import") (part "rcl_R-US_R0603"))
    )
    (comp (ref "R39")
      (value "4.7K")
      (footprint "eagle-import:R0603")
      (libsource (lib "eagle-import") (part "rcl_R-US_R0603"))
    )
    (comp (ref "R40")
      (value "4.7K")
      (footprint "eagle-import:R0603")
      (libsource (lib "eagle-import") (part "rcl_R-US_R0603"))
    )
    (comp (ref "R41")
      (value "39")
      (footprint "eagle-import:R0603")
      (libsource (lib "eagle-import") (part "rcl_R-US_R0603"))
    )
    (comp (ref "R42")
      (value "39")
      (footprint "eagle-import:R0603")
      (libsource (lib "eagle-import") (part "rcl_R-US_R0603"))
    )
    (comp (ref "R43")
      (value "100K")
      (footprint "eagle-import:R0603")
      (libsource (lib "eagle-import") (part "rcl_R-US_R0603"))
    )
    (comp (ref "R44")
      (value "100")
      (footprint "eagle-import:R0603")
      (libsource (lib "eagle-import") (part "rcl_R-US_R0603"))
    )
    (comp (ref "R45")
      (value "100K")
      (footprint "eagle-import:R0603")
      (libsource (lib "eagle-import") (part "rcl_R-US_R0603"))
    )
    (comp (ref "R46")
      (value "100K")
      (footprint "eagle-import:R0603")
      (libsource (lib "eagle-import") (part "rcl_R-US_R0603"))
    )
    (comp (ref "RED_BOT")
      (value "SOLDERJUMPERNO")
      (footprint "eagle-import:SJ_2S-NO")
      (libsource (lib "eagle-import") (part "SOLDERJUMPERNO"))
    )
    (comp (ref "RED_TOP")
      (value "SOLDERJUMPERNO")
      (footprint "eagle-import:SJ_2S-NO")
      (libsource (lib "eagle-import") (part "SOLDERJUMPERNO"))
    )
    (comp (ref "RESET")
      (value "TACT_SWITCH-PTS-525")
      (footprint "eagle-import:PTS-525")
      (libsource (lib "eagle-import") (part "TACT_SWITCH-PTS-525"))
    )
    (comp (ref "RESET_CC8531")
      (value "SOLDERJUMPERNO")
      (footprint "eagle-import:SJ_2S-NO")
      (libsource (lib "eagle-import") (part "SOLDERJUMPERNO"))
    )
    (comp (ref "RESET_CODEC")
      (value "SOLDERJUMPERNO")
      (footprint "eagle-import:SJ_2S-NO")
      (libsource (lib "eagle-import") (part "SOLDERJUMPERNO"))
    )
    (comp (ref "SCLK")
      (value "SOLDERJUMPERNO")
      (footprint "eagle-import:SJ_2S-NO")
      (libsource (lib "eagle-import") (part "SOLDERJUMPERNO"))
    )
    (comp (ref "SCLK2")
      (value "SOLDERJUMPERNO")
      (footprint "eagle-import:SJ_2S-NO")
      (libsource (lib "eagle-import") (part "SOLDERJUMPERNO"))
    )
    (comp (ref "SCLK3")
      (value "SOLDERJUMPERNO")
      (footprint "eagle-import:SJ_2S-NO")
      (libsource (lib "eagle-import") (part "SOLDERJUMPERNO"))
    )
    (comp (ref "SCLK4")
      (value "SOLDERJUMPERNO")
      (footprint "eagle-import:SJ_2S-NO")
      (libsource (lib "eagle-import") (part "SOLDERJUMPERNO"))
    )
    (comp (ref "SMA")
      (value "SMA-REVSMA-0.62")
      (footprint "eagle-import:CONREVSMA003.062")
      (libsource (lib "eagle-import") (part "SMA-REVSMA-0.62"))
    )
    (comp (ref "SW1")
      (value "TOUCH_PAD-CIRCLE-15MM")
      (footprint "eagle-import:TOUCH-CIRCLE-15MM")
      (libsource (lib "eagle-import") (part "TOUCH_PAD-CIRCLE-15MM"))
    )
    (comp (ref "SW4")
      (value "TOUCH_PAD-CIRCLE-15MM")
      (footprint "eagle-import:TOUCH-CIRCLE-15MM")
      (libsource (lib "eagle-import") (part "TOUCH_PAD-CIRCLE-15MM"))
    )
    (comp (ref "SW5")
      (value "TOUCH_PAD-CIRCLE-15MM")
      (footprint "eagle-import:TOUCH-CIRCLE-15MM")
      (libsource (lib "eagle-import") (part "TOUCH_PAD-CIRCLE-15MM"))
    )
    (comp (ref "SW6")
      (value "TOUCH_PAD-CIRCLE-15MM")
      (footprint "eagle-import:TOUCH-CIRCLE-15MM")
      (libsource (lib "eagle-import") (part "TOUCH_PAD-CIRCLE-15MM"))
    )
    (comp (ref "SW7")
      (value "TOUCH_PAD-CIRCLE-15MM")
      (footprint "eagle-import:TOUCH-CIRCLE-15MM")
      (libsource (lib "eagle-import") (part "TOUCH_PAD-CIRCLE-15MM"))
    )
    (comp (ref "SW8")
      (value "TOUCH_PAD-CIRCLE-15MM")
      (footprint "eagle-import:TOUCH-CIRCLE-15MM")
      (libsource (lib "eagle-import") (part "TOUCH_PAD-CIRCLE-15MM"))
    )
    (comp (ref "SW9")
      (value "TOUCH_PAD-CIRCLE-15MM")
      (footprint "eagle-import:TOUCH-CIRCLE-15MM")
      (libsource (lib "eagle-import") (part "TOUCH_PAD-CIRCLE-15MM"))
    )
    (comp (ref "SW10")
      (value "TOUCH_PAD-CIRCLE-15MM")
      (footprint "eagle-import:TOUCH-CIRCLE-15MM")
      (libsource (lib "eagle-import") (part "TOUCH_PAD-CIRCLE-15MM"))
    )
    (comp (ref "U1")
      (value "CC8531")
      (footprint "eagle-import:S-PVQFN-N40")
      (libsource (lib "eagle-import") (part "CC8531"))
    )
    (comp (ref "U2")
      (value "CC2591")
      (footprint "eagle-import:S-PVQFN-N16")
      (libsource (lib "eagle-import") (part "CC2591"))
    )
    (comp (ref "U3")
      (value "TLV320AIC3204")
      (footprint "eagle-import:S-PVQFN-N32")
      (libsource (lib "eagle-import") (part "TLV320AIC3204"))
    )
    (comp (ref "U5")
      (value "MCP1826-SOT223")
      (footprint "eagle-import:SOT-223")
      (libsource (lib "eagle-import") (part "MCP1826-SOT223"))
    )
    (comp (ref "U6")
      (value "LTC4088-2")
      (footprint "eagle-import:DFN-14")
      (libsource (lib "eagle-import") (part "LTC4088-1/2"))
    )
    (comp (ref "U7")
      (value "ATSAM3X8E_ALT-LQFP-144")
      (footprint "eagle-import:LQFP-144")
      (libsource (lib "eagle-import") (part "ATSAM3X8E_ALT-LQFP-144"))
    )
    (comp (ref "U8")
      (value "AT42QT1110-TQFP")
      (footprint "eagle-import:S-PQFP-N32")
      (libsource (lib "eagle-import") (part "AT42QT1110-TQFP"))
    )
    (comp (ref "U9")
      (value "LM4881")
      (footprint "eagle-import:SO08")
      (libsource (lib "eagle-import") (part "LM4881"))
    )
    (comp (ref "USB1")
      (value "USB_MICRO_AB")
      (footprint "eagle-import:USB_MICRO_AB")
      (libsource (lib "eagle-import") (part "USB_MICRO_AB"))
    )
    (comp (ref "USB2")
      (value "USB_MICRO_AB")
      (footprint "eagle-import:USB_MICRO_AB")
      (libsource (lib "eagle-import") (part "USB_MICRO_AB"))
    )
    (comp (ref "USB_SENSE")
      (value "SOLDERJUMPERNO")
      (footprint "eagle-import:SJ_2S-NO")
      (libsource (lib "eagle-import") (part "SOLDERJUMPERNO"))
    )
    (comp (ref "VDD_SD")
      (value "SOLDERJUMPERNO")
      (footprint "eagle-import:SJ_2S-NO")
      (libsource (lib "eagle-import") (part "SOLDERJUMPERNO"))
    )
    (comp (ref "WCLK")
      (value "SOLDERJUMPERNO")
      (footprint "eagle-import:SJ_2S-NO")
      (libsource (lib "eagle-import") (part "SOLDERJUMPERNO"))
    )
    (comp (ref "WCLK2")
      (value "SOLDERJUMPERNO")
      (footprint "eagle-import:SJ_2S-NO")
      (libsource (lib "eagle-import") (part "SOLDERJUMPERNO"))
    )
    (comp (ref "X1")
      (value "48MHz")
      (footprint "eagle-import:ABM3C")
      (libsource (lib "eagle-import") (part "XTAL-ABRACONABM3C"))
    )
    (comp (ref "X3")
      (value "12MHz")
      (footprint "eagle-import:ABM8G")
      (libsource (lib "eagle-import") (part "XTAL-ABRACONABM8G"))
    )
  )
  (nets
    (net (code "1") (name "/AGND") (class "Default")
      (node (ref "C31") (pin "2") (pinfunction "2_2") (pintype "passive"))
      (node (ref "C33") (pin "2") (pinfunction "2_2") (pintype "passive"))
      (node (ref "C34") (pin "2") (pinfunction "2_2") (pintype "passive"))
      (node (ref "C40") (pin "2") (pinfunction "2_2") (pintype "passive"))
      (node (ref "C41") (pin "2") (pinfunction "2_2") (pintype "passive"))
      (node (ref "C42") (pin "2") (pinfunction "2_2") (pintype "passive"))
      (node (ref "C48") (pin "2") (pinfunction "2_2") (pintype "passive"))
      (node (ref "C50") (pin "2") (pinfunction "2_2") (pintype "passive"))
      (node (ref "LINE_IN") (pin "5") (pinfunction "GND_5") (pintype "bidirectional"))
      (node (ref "PHONE_OUT") (pin "5") (pinfunction "GND_5") (pintype "bidirectional"))
      (node (ref "R17") (pin "2") (pinfunction "2_2") (pintype "passive"))
      (node (ref "R23") (pin "1") (pinfunction "1_1") (pintype "passive"))
      (node (ref "R25") (pin "1") (pinfunction "1_1") (pintype "passive"))
      (node (ref "U3") (pin "17") (pinfunction "AVSS_17") (pintype "bidirectional"))
      (node (ref "U9") (pin "2") (pinfunction "VSS_2") (pintype "bidirectional"))
    )
    (net (code "2") (name "/AUX_VDD") (class "Default")
      (node (ref "C63") (pin "1") (pinfunction "1_1") (pintype "passive"))
      (node (ref "C64") (pin "1") (pinfunction "1_1") (pintype "passive"))
      (node (ref "C65") (pin "1") (pinfunction "1_1") (pintype "passive"))
      (node (ref "L18") (pin "1") (pinfunction "1_1") (pintype "passive"))
      (node (ref "LED_LL") (pin "2") (pinfunction "A_2") (pintype "passive"))
      (node (ref "LED_LL") (pin "2-2") (pinfunction "A_2-2") (pintype "passive"))
      (node (ref "LED_LR") (pin "2") (pinfunction "A_2") (pintype "passive"))
      (node (ref "LED_LR") (pin "2-2") (pinfunction "A_2-2") (pintype "passive"))
      (node (ref "LED_UL") (pin "2") (pinfunction "A_2") (pintype "passive"))
      (node (ref "LED_UL") (pin "2-2") (pinfunction "A_2-2") (pintype "passive"))
      (node (ref "LED_UR") (pin "2") (pinfunction "A_2") (pintype "passive"))
      (node (ref "LED_UR") (pin "2-2") (pinfunction "A_2-2") (pintype "passive"))
      (node (ref "R36") (pin "2") (pinfunction "2_2") (pintype "passive"))
      (node (ref "U8") (pin "18") (pinfunction "VDD_18") (pintype "bidirectional"))
      (node (ref "U8") (pin "4") (pinfunction "VDD_4") (pintype "bidirectional"))
    )
    (net (code "3") (name "/AUX_VSS") (class "Default")
      (node (ref "C63") (pin "2") (pinfunction "2_2") (pintype "passive"))
      (node (ref "C64") (pin "2") (pinfunction "2_2") (pintype "passive"))
      (node (ref "Q2") (pin "2") (pinfunction "S_2") (pintype "passive"))
      (node (ref "Q3") (pin "2") (pinfunction "S_2") (pintype "passive"))
      (node (ref "Q4") (pin "2") (pinfunction "S_2") (pintype "passive"))
      (node (ref "Q5") (pin "2") (pinfunction "S_2") (pintype "passive"))
      (node (ref "Q6") (pin "2") (pinfunction "S_2") (pintype "passive"))
      (node (ref "Q7") (pin "2") (pinfunction "S_2") (pintype "passive"))
      (node (ref "U8") (pin "21") (pinfunction "VSS_21") (pintype "bidirectional"))
      (node (ref "U8") (pin "5") (pinfunction "VSS_5") (pintype "bidirectional"))
    )
    (net (code "4") (name "/AUX_~{CHANGE}") (class "Default")
      (node (ref "!CHANGE") (pin "1") (pinfunction "1_1") (pintype "passive"))
      (node (ref "U8") (pin "28") (pinfunction "~{CHANGE}_28") (pintype "bidirectional"))
    )
    (net (code "5") (name "/AVDD") (class "Default")
      (node (ref "C10") (pin "1") (pinfunction "1_1") (pintype "passive"))
      (node (ref "C11") (pin "1") (pinfunction "1_1") (pintype "passive"))
      (node (ref "C12") (pin "1") (pinfunction "1_1") (pintype "passive"))
      (node (ref "C15") (pin "1") (pinfunction "1_1") (pintype "passive"))
      (node (ref "C16") (pin "1") (pinfunction "1_1") (pintype "passive"))
      (node (ref "C17") (pin "1") (pinfunction "1_1") (pintype "passive"))
      (node (ref "C18") (pin "1") (pinfunction "1_1") (pintype "passive"))
      (node (ref "C19") (pin "1") (pinfunction "1_1") (pintype "passive"))
      (node (ref "C2") (pin "1") (pinfunction "1_1") (pintype "passive"))
      (node (ref "C20") (pin "1") (pinfunction "1_1") (pintype "passive"))
      (node (ref "C21") (pin "1") (pinfunction "1_1") (pintype "passive"))
      (node (ref "C22") (pin "1") (pinfunction "1_1") (pintype "passive"))
      (node (ref "C8") (pin "1") (pinfunction "1_1") (pintype "passive"))
      (node (ref "C9") (pin "1") (pinfunction "1_1") (pintype "passive"))
      (node (ref "L2") (pin "1") (pinfunction "1_1") (pintype "passive"))
      (node (ref "L3") (pin "1") (pinfunction "1_1") (pintype "passive"))
      (node (ref "R9") (pin "2") (pinfunction "2_2") (pintype "passive"))
      (node (ref "U1") (pin "20") (pinfunction "AVDD1_20") (pintype "bidirectional"))
      (node (ref "U1") (pin "23") (pinfunction "AVDD2_23") (pintype "bidirectional"))
      (node (ref "U1") (pin "26") (pinfunction "AVDD3_26") (pintype "bidirectional"))
      (node (ref "U1") (pin "27") (pinfunction "AVDD4_27") (pintype "bidirectional"))
      (node (ref "U1") (pin "28") (pinfunction "AVDD5_28") (pintype "bidirectional"))
      (node (ref "U1") (pin "31") (pinfunction "AVDD6_31") (pintype "bidirectional"))
      (node (ref "U2") (pin "1") (pinfunction "AVDD_PA1_1") (pintype "bidirectional"))
      (node (ref "U2") (pin "10") (pinfunction "AVDD_PA2_10") (pintype "bidirectional"))
      (node (ref "U2") (pin "13") (pinfunction "AVDD_LNA_13") (pintype "bidirectional"))
      (node (ref "U2") (pin "16") (pinfunction "AVDD_BIAS_16") (pintype "bidirectional"))
    )
    (net (code "6") (name "/AVDD_CODEC") (class "Default")
      (node (ref "C31") (pin "1") (pinfunction "1_1") (pintype "passive"))
      (node (ref "C34") (pin "1") (pinfunction "1_1") (pintype "passive"))
      (node (ref "C40") (pin "1") (pinfunction "1_1") (pintype "passive"))
      (node (ref "C41") (pin "1") (pinfunction "1_1") (pintype "passive"))
      (node (ref "C42") (pin "1") (pinfunction "1_1") (pintype "passive"))
      (node (ref "L14") (pin "1") (pinfunction "1_1") (pintype "passive"))
      (node (ref "R22") (pin "2") (pinfunction "2_2") (pintype "passive"))
      (node (ref "R24") (pin "2") (pinfunction "2_2") (pintype "passive"))
      (node (ref "R31") (pin "2") (pinfunction "2_2") (pintype "passive"))
      (node (ref "U3") (pin "26") (pinfunction "LDOIN_26") (pintype "bidirectional"))
      (node (ref "U9") (pin "6") (pinfunction "VDD_6") (pintype "bidirectional"))
    )
    (net (code "7") (name "/AVR_VDD") (class "Default")
      (node (ref "C35") (pin "1") (pinfunction "1_1") (pintype "passive"))
      (node (ref "C46") (pin "1") (pinfunction "1_1") (pintype "passive"))
      (node (ref "C47") (pin "1") (pinfunction "1_1") (pintype "passive"))
      (node (ref "C69") (pin "1") (pinfunction "1_1") (pintype "passive"))
      (node (ref "ERASE") (pin "3") (pinfunction "3_3") (pintype "bidirectional"))
      (node (ref "JTAG") (pin "1") (pinfunction "1_1") (pintype "bidirectional"))
      (node (ref "L16") (pin "1") (pinfunction "1_1") (pintype "passive"))
      (node (ref "R11") (pin "2") (pinfunction "2_2") (pintype "passive"))
      (node (ref "R14") (pin "2") (pinfunction "2_2") (pintype "passive"))
      (node (ref "R27") (pin "2") (pinfunction "2_2") (pintype "passive"))
      (node (ref "R43") (pin "1") (pinfunction "1_1") (pintype "passive"))
      (node (ref "R44") (pin "2") (pinfunction "2_2") (pintype "passive"))
      (node (ref "R45") (pin "2") (pinfunction "2_2") (pintype "passive"))
      (node (ref "R46") (pin "2") (pinfunction "2_2") (pintype "passive"))
      (node (ref "R6") (pin "2") (pinfunction "2_2") (pintype "passive"))
      (node (ref "U7") (pin "105") (pinfunction "VDDIO_3_105") (pintype "bidirectional"))
      (node (ref "U7") (pin "11") (pinfunction "VDDIO_1_11") (pintype "bidirectional"))
      (node (ref "U7") (pin "125") (pinfunction "VDDIO_4_125") (pintype "bidirectional"))
      (node (ref "U7") (pin "41") (pinfunction "VDDUTMI_41") (pintype "bidirectional"))
      (node (ref "U7") (pin "52") (pinfunction "VDDBU_52") (pintype "bidirectional"))
      (node (ref "U7") (pin "57") (pinfunction "VDDIN_57") (pintype "bidirectional"))
      (node (ref "U7") (pin "62") (pinfunction "VDDIO_2_62") (pintype "bidirectional"))
      (node (ref "U7") (pin "73") (pinfunction "VDDANA_73") (pintype "bidirectional"))
      (node (ref "U7") (pin "75") (pinfunction "ADVREF_75") (pintype "bidirectional"))
      (node (ref "VDD_SD") (pin "2") (pinfunction "2_2") (pintype "passive"))
    )
    (net (code "8") (name "/DVDD_CODEC") (class "Default")
      (node (ref "C32") (pin "1") (pinfunction "1_1") (pintype "passive"))
      (node (ref "C45") (pin "1") (pinfunction "1_1") (pintype "passive"))
      (node (ref "L15") (pin "1") (pinfunction "1_1") (pintype "passive"))
      (node (ref "U3") (pin "12") (pinfunction "SPI_SELECT_12") (pintype "bidirectional"))
      (node (ref "U3") (pin "30") (pinfunction "LDO_SELECT_30") (pintype "bidirectional"))
      (node (ref "U3") (pin "6") (pinfunction "IOVDD_6") (pintype "bidirectional"))
    )
    (net (code "9") (name "/IOVDD") (class "Default")
      (node (ref "C1") (pin "1") (pinfunction "1_1") (pintype "passive"))
      (node (ref "C3") (pin "1") (pinfunction "1_1") (pintype "passive"))
      (node (ref "C4") (pin "1") (pinfunction "1_1") (pintype "passive"))
      (node (ref "C5") (pin "1") (pinfunction "1_1") (pintype "passive"))
      (node (ref "C6") (pin "1") (pinfunction "1_1") (pintype "passive"))
      (node (ref "C7") (pin "1") (pinfunction "1_1") (pintype "passive"))
      (node (ref "CC8531") (pin "A") (pinfunction "A_A") (pintype "passive"))
      (node (ref "L1") (pin "1") (pinfunction "1_1") (pintype "passive"))
      (node (ref "U1") (pin "10") (pinfunction "IOVDD1_10") (pintype "bidirectional"))
      (node (ref "U1") (pin "12") (pinfunction "IOVDD2_12") (pintype "bidirectional"))
      (node (ref "U1") (pin "18") (pinfunction "IOVDD3_18") (pintype "bidirectional"))
      (node (ref "U1") (pin "37") (pinfunction "IOVDD4_37") (pintype "bidirectional"))
      (node (ref "U1") (pin "40") (pinfunction "DVDD_40") (pintype "bidirectional"))
    )
    (net (code "10") (name "/VBUS") (class "Default")
      (node (ref "C51") (pin "1") (pinfunction "1_1") (pintype "passive"))
      (node (ref "R18") (pin "2") (pinfunction "2_2") (pintype "passive"))
      (node (ref "U6") (pin "11") (pinfunction "VBUS_11") (pintype "bidirectional"))
      (node (ref "U6") (pin "13") (pinfunction "D0_13") (pintype "bidirectional"))
      (node (ref "U7") (pin "39") (pinfunction "VBUS_39") (pintype "bidirectional"))
      (node (ref "USB1") (pin "1") (pinfunction "VBUS_1") (pintype "bidirectional"))
      (node (ref "USB2") (pin "1") (pinfunction "VBUS_1") (pintype "bidirectional"))
    )
    (net (code "11") (name "/VDDCORE") (class "Default")
      (node (ref "C43") (pin "1") (pinfunction "1_1") (pintype "passive"))
      (node (ref "C44") (pin "1") (pinfunction "1_1") (pintype "passive"))
      (node (ref "U7") (pin "10") (pinfunction "VDDCORE_1_10") (pintype "bidirectional"))
      (node (ref "U7") (pin "104") (pinfunction "VDDCORE_4_104") (pintype "bidirectional"))
      (node (ref "U7") (pin "124") (pinfunction "VDDCORE_5_124") (pintype "bidirectional"))
      (node (ref "U7") (pin "34") (pinfunction "VDDPLL_34") (pintype "bidirectional"))
      (node (ref "U7") (pin "45") (pinfunction "VDDCORE_2_45") (pintype "bidirectional"))
      (node (ref "U7") (pin "56") (pinfunction "VDDOUT_56") (pintype "bidirectional"))
      (node (ref "U7") (pin "61") (pinfunction "VDDCORE_3_61") (pintype "bidirectional"))
    )
    (net (code "12") (name "/X_~{PAIR}") (class "Default")
      (node (ref "!PAIR") (pin "1") (pinfunction "1_1") (pintype "passive"))
      (node (ref "U1") (pin "7") (pinfunction "GIO1_7") (pintype "bidirectional"))
    )
    (net (code "13") (name "/~{AVR_LED2}") (class "Default")
      (node (ref "AVR1") (pin "C") (pinfunction "C_C") (pintype "passive"))
      (node (ref "U7") (pin "68") (pinfunction "PB27_68") (pintype "bidirectional"))
    )
    (net (code "14") (name "/~{AVR_LED3}") (class "Default")
      (node (ref "AVR2") (pin "C") (pinfunction "C_C") (pintype "passive"))
      (node (ref "U7") (pin "71") (pinfunction "PA19_71") (pintype "bidirectional"))
    )
    (net (code "15") (name "/~{AVR_LED}") (class "Default")
      (node (ref "AVR") (pin "C") (pinfunction "C_C") (pintype "passive"))
      (node (ref "U7") (pin "72") (pinfunction "PA20_72") (pintype "bidirectional"))
    )
    (net (code "16") (name "/~{CHANGE}") (class "Default")
      (node (ref "!CHANGE") (pin "2") (pinfunction "2_2") (pintype "passive"))
      (node (ref "U7") (pin "32") (pinfunction "PD10_32") (pintype "bidirectional"))
    )
    (net (code "17") (name "/~{PAIR}") (class "Default")
      (node (ref "!PAIR") (pin "2") (pinfunction "2_2") (pintype "passive"))
      (node (ref "U7") (pin "21") (pinfunction "PD8_21") (pintype "bidirectional"))
    )
    (net (code "18") (name "/~{RESET}") (class "Default")
      (node (ref "C69") (pin "2") (pinfunction "2_2") (pintype "passive"))
      (node (ref "JTAG") (pin "10") (pinfunction "10_10") (pintype "bidirectional"))
      (node (ref "R46") (pin "1") (pinfunction "1_1") (pintype "passive"))
      (node (ref "RESET") (pin "1") (pinfunction "1_1") (pintype "bidirectional"))
      (node (ref "U7") (pin "47") (pinfunction "NRSTB_47") (pintype "bidirectional"))
    )
    (net (code "19") (name "/~{SD_CARD}") (class "Default")
      (node (ref "!SD_CARD") (pin "1") (pinfunction "1_1") (pintype "passive"))
      (node (ref "U7") (pin "66") (pinfunction "PC8_66") (pintype "bidirectional"))
    )
    (net (code "20") (name "3.3V") (class "Default")
      (node (ref "AMP_VDD") (pin "2") (pinfunction "2_2") (pintype "passive"))
      (node (ref "AUX_VDD") (pin "2") (pinfunction "2_2") (pintype "passive"))
      (node (ref "AVDD") (pin "2") (pinfunction "2_2") (pintype "passive"))
      (node (ref "AVDD_CODEC") (pin "2") (pinfunction "2_2") (pintype "passive"))
      (node (ref "AVR_VDD") (pin "2") (pinfunction "2_2") (pintype "passive"))
      (node (ref "C53") (pin "1") (pinfunction "1_1") (pintype "passive"))
      (node (ref "CC_DEBUG") (pin "2") (pinfunction "2_2") (pintype "bidirectional"))
      (node (ref "DVDD_CODEC") (pin "2") (pinfunction "2_2") (pintype "passive"))
      (node (ref "EXT") (pin "1") (pinfunction "1_1") (pintype "passive"))
      (node (ref "IOVDD") (pin "2") (pinfunction "2_2") (pintype "passive"))
      (node (ref "R3") (pin "2") (pinfunction "2_2") (pintype "passive"))
      (node (ref "U5") (pin "3") (pinfunction "VOUT_3") (pintype "bidirectional"))
    )
    (net (code "21") (name "AUDIO") (class "Default")
      (node (ref "AUDIO") (pin "2") (pinfunction "2_2") (pintype "passive"))
      (node (ref "U7") (pin "85") (pinfunction "PA2_85") (pintype "bidirectional"))
    )
    (net (code "22") (name "AUX_BLUE_BOT") (class "Default")
      (node (ref "BLUE_BOT") (pin "1") (pinfunction "1_1") (pintype "passive"))
      (node (ref "Q7") (pin "1") (pinfunction "G_1") (pintype "passive"))
    )
    (net (code "23") (name "AUX_BLUE_TOP") (class "Default")
      (node (ref "BLUE_TOP") (pin "1") (pinfunction "1_1") (pintype "passive"))
      (node (ref "Q4") (pin "1") (pinfunction "G_1") (pintype "passive"))
    )
    (net (code "24") (name "AUX_CS") (class "Default")
      (node (ref "CS_TOUCH") (pin "1") (pinfunction "1_1") (pintype "passive"))
      (node (ref "U8") (pin "14") (pinfunction "~{SS}_14") (pintype "bidirectional"))
    )
    (net (code "25") (name "AUX_GREEN_BOT") (class "Default")
      (node (ref "GREEN_BOT") (pin "1") (pinfunction "1_1") (pintype "passive"))
      (node (ref "Q6") (pin "1") (pinfunction "G_1") (pintype "passive"))
    )
    (net (code "26") (name "AUX_GREEN_TOP") (class "Default")
      (node (ref "GREEN_TOP") (pin "1") (pinfunction "1_1") (pintype "passive"))
      (node (ref "Q3") (pin "1") (pinfunction "G_1") (pintype "passive"))
    )
    (net (code "27") (name "AUX_MISO") (class "Default")
      (node (ref "MISO3") (pin "1") (pinfunction "1_1") (pintype "passive"))
      (node (ref "U8") (pin "16") (pinfunction "MISO_16") (pintype "bidirectional"))
    )
    (net (code "28") (name "AUX_MOSI") (class "Default")
      (node (ref "MOSI3") (pin "1") (pinfunction "1_1") (pintype "passive"))
      (node (ref "U8") (pin "15") (pinfunction "MOSI_15") (pintype "bidirectional"))
    )
    (net (code "29") (name "AUX_RED_BOT") (class "Default")
      (node (ref "Q5") (pin "1") (pinfunction "G_1") (pintype "passive"))
      (node (ref "RED_BOT") (pin "1") (pinfunction "1_1") (pintype "passive"))
    )
    (net (code "30") (name "AUX_RED_TOP") (class "Default")
      (node (ref "Q2") (pin "1") (pinfunction "G_1") (pintype "passive"))
      (node (ref "RED_TOP") (pin "1") (pinfunction "1_1") (pintype "passive"))
    )
    (net (code "31") (name "AUX_SCLK") (class "Default")
      (node (ref "SCLK3") (pin "1") (pinfunction "1_1") (pintype "passive"))
      (node (ref "U8") (pin "17") (pinfunction "SCK_17") (pintype "bidirectional"))
    )
    (net (code "32") (name "BCLK") (class "Default")
      (node (ref "BCLK") (pin "2") (pinfunction "2_2") (pintype "passive"))
      (node (ref "BCLK2") (pin "1") (pinfunction "1_1") (pintype "passive"))
      (node (ref "U3") (pin "2") (pinfunction "BCLK_2") (pintype "bidirectional"))
    )
    (net (code "33") (name "BLUE_BOT") (class "Default")
      (node (ref "BLUE_BOT") (pin "2") (pinfunction "2_2") (pintype "passive"))
      (node (ref "U7") (pin "135") (pinfunction "PC24_135") (pintype "bidirectional"))
    )
    (net (code "34") (name "BLUE_TOP") (class "Default")
      (node (ref "BLUE_TOP") (pin "2") (pinfunction "2_2") (pintype "passive"))
      (node (ref "U7") (pin "134") (pinfunction "PC23_134") (pintype "bidirectional"))
    )
    (net (code "35") (name "CS_CC8531") (class "Default")
      (node (ref "CS_CC8531") (pin "2") (pinfunction "2_2") (pintype "passive"))
      (node (ref "U7") (pin "22") (pinfunction "PD9_22") (pintype "bidirectional"))
    )
    (net (code "36") (name "CS_CODEC") (class "Default")
      (node (ref "CS_CODEC") (pin "2") (pinfunction "2_2") (pintype "passive"))
      (node (ref "U7") (pin "15") (pinfunction "PD2_15") (pintype "bidirectional"))
    )
    (net (code "37") (name "CS_SD") (class "Default")
      (node (ref "CS_SD") (pin "1") (pinfunction "1_1") (pintype "passive"))
      (node (ref "U7") (pin "67") (pinfunction "PC9_67") (pintype "bidirectional"))
    )
    (net (code "38") (name "CS_TOUCH") (class "Default")
      (node (ref "CS_TOUCH") (pin "2") (pinfunction "2_2") (pintype "passive"))
      (node (ref "U7") (pin "26") (pinfunction "PA7_26") (pintype "bidirectional"))
    )
    (net (code "39") (name "C_AUDIO") (class "Default")
      (node (ref "AUDIO") (pin "1") (pinfunction "1_1") (pintype "passive"))
      (node (ref "C36") (pin "1") (pinfunction "1_1") (pintype "passive"))
      (node (ref "R12") (pin "1") (pinfunction "1_1") (pintype "passive"))
      (node (ref "U9") (pin "7") (pinfunction "OUTA_7") (pintype "bidirectional"))
    )
    (net (code "40") (name "C_CS_CODEC") (class "Default")
      (node (ref "CS_CODEC") (pin "1") (pinfunction "1_1") (pintype "passive"))
      (node (ref "U3") (pin "9") (pinfunction "SCL/SSZ_9") (pintype "bidirectional"))
    )
    (net (code "41") (name "C_LINEIN_SENSE") (class "Default")
      (node (ref "LINEIN_SENSE") (pin "1") (pinfunction "1_1") (pintype "passive"))
      (node (ref "LINE_IN") (pin "3") (pinfunction "L_SW_3") (pintype "bidirectional"))
      (node (ref "R22") (pin "1") (pinfunction "1_1") (pintype "passive"))
    )
    (net (code "42") (name "C_MISO") (class "Default")
      (node (ref "MISO2") (pin "1") (pinfunction "1_1") (pintype "passive"))
      (node (ref "U3") (pin "11") (pinfunction "MISO/MFP4_11") (pintype "bidirectional"))
    )
    (net (code "43") (name "C_MOSI") (class "Default")
      (node (ref "MOSI2") (pin "1") (pinfunction "1_1") (pintype "passive"))
      (node (ref "U3") (pin "10") (pinfunction "SDA/MOSI_10") (pintype "bidirectional"))
    )
    (net (code "44") (name "C_PHONE_SENSE") (class "Default")
      (node (ref "PHONE_OUT") (pin "3") (pinfunction "L_SW_3") (pintype "bidirectional"))
      (node (ref "PHONE_SENSE") (pin "1") (pinfunction "1_1") (pintype "passive"))
      (node (ref "R24") (pin "1") (pinfunction "1_1") (pintype "passive"))
    )
    (net (code "45") (name "C_RESET_CODEC") (class "Default")
      (node (ref "RESET_CODEC") (pin "1") (pinfunction "1_1") (pintype "passive"))
      (node (ref "U3") (pin "31") (pinfunction "~{RESET}_31") (pintype "bidirectional"))
    )
    (net (code "46") (name "C_SCLK") (class "Default")
      (node (ref "SCLK2") (pin "1") (pinfunction "1_1") (pintype "passive"))
      (node (ref "U3") (pin "8") (pinfunction "SCLK/MFP3_8") (pintype "bidirectional"))
    )
    (net (code "47") (name "D+_CC8531") (class "Default")
      (node (ref "R2") (pin "2") (pinfunction "2_2") (pintype "passive"))
      (node (ref "R7") (pin "2") (pinfunction "2_2") (pintype "passive"))
      (node (ref "USB1") (pin "3") (pinfunction "D+_3") (pintype "bidirectional"))
    )
    (net (code "48") (name "D+_UC") (class "Default")
      (node (ref "R42") (pin "2") (pinfunction "2_2") (pintype "passive"))
      (node (ref "U7") (pin "37") (pinfunction "DHSDP_37") (pintype "bidirectional"))
      (node (ref "USB2") (pin "3") (pinfunction "D+_3") (pintype "bidirectional"))
    )
    (net (code "49") (name "D-_CC8531") (class "Default")
      (node (ref "R1") (pin "2") (pinfunction "2_2") (pintype "passive"))
      (node (ref "USB1") (pin "2") (pinfunction "D-_2") (pintype "bidirectional"))
    )
    (net (code "50") (name "D-_UC") (class "Default")
      (node (ref "R41") (pin "2") (pinfunction "2_2") (pintype "passive"))
      (node (ref "U7") (pin "38") (pinfunction "DHSDM_38") (pintype "bidirectional"))
      (node (ref "USB2") (pin "2") (pinfunction "D-_2") (pintype "bidirectional"))
    )
    (net (code "51") (name "DIN") (class "Default")
      (node (ref "DIN") (pin "2") (pinfunction "2_2") (pintype "passive"))
      (node (ref "DOUT2") (pin "1") (pinfunction "1_1") (pintype "passive"))
      (node (ref "U3") (pin "4") (pinfunction "DIN/MFP1_4") (pintype "bidirectional"))
    )
    (net (code "52") (name "DOUT") (class "Default")
      (node (ref "DIN2") (pin "1") (pinfunction "1_1") (pintype "passive"))
      (node (ref "DOUT") (pin "2") (pinfunction "2_2") (pintype "passive"))
      (node (ref "U3") (pin "5") (pinfunction "DOUT/MFP2_5") (pintype "bidirectional"))
    )
    (net (code "53") (name "ERASE") (class "Default")
      (node (ref "ERASE") (pin "1") (pinfunction "1_1") (pintype "bidirectional"))
      (node (ref "U7") (pin "130") (pinfunction "PC0_130") (pintype "bidirectional"))
    )
    (net (code "54") (name "GND") (class "Default")
      (node (ref "BATTERY") (pin "-") (pinfunction "N_-") (pintype "passive"))
      (node (ref "BATTERY") (pin "X1") (pinfunction "CASE_X1") (pintype "passive"))
      (node (ref "BATTERY") (pin "X2") (pinfunction "CASE_X2") (pintype "passive"))
      (node (ref "C1") (pin "2") (pinfunction "2_2") (pintype "passive"))
      (node (ref "C10") (pin "2") (pinfunction "2_2") (pintype "passive"))
      (node (ref "C11") (pin "2") (pinfunction "2_2") (pintype "passive"))
      (node (ref "C12") (pin "2") (pinfunction "2_2") (pintype "passive"))
      (node (ref "C13") (pin "2") (pinfunction "2_2") (pintype "passive"))
      (node (ref "C14") (pin "2") (pinfunction "2_2") (pintype "passive"))
      (node (ref "C15") (pin "2") (pinfunction "2_2") (pintype "passive"))
      (node (ref "C16") (pin "2") (pinfunction "2_2") (pintype "passive"))
      (node (ref "C17") (pin "2") (pinfunction "2_2") (pintype "passive"))
      (node (ref "C18") (pin "2") (pinfunction "2_2") (pintype "passive"))
      (node (ref "C19") (pin "2") (pinfunction "2_2") (pintype "passive"))
      (node (ref "C2") (pin "2") (pinfunction "2_2") (pintype "passive"))
      (node (ref "C20") (pin "2") (pinfunction "2_2") (pintype "passive"))
      (node (ref "C21") (pin "2") (pinfunction "2_2") (pintype "passive"))
      (node (ref "C22") (pin "2") (pinfunction "2_2") (pintype "passive"))
      (node (ref "C23") (pin "2") (pinfunction "2_2") (pintype "passive"))
      (node (ref "C24") (pin "2") (pinfunction "2_2") (pintype "passive"))
      (node (ref "C27") (pin "2") (pinfunction "2_2") (pintype "passive"))
      (node (ref "C28") (pin "2") (pinfunction "2_2") (pintype "passive"))
      (node (ref "C29") (pin "2") (pinfunction "2_2") (pintype "passive"))
      (node (ref "C3") (pin "2") (pinfunction "2_2") (pintype "passive"))
      (node (ref "C30") (pin "2") (pinfunction "2_2") (pintype "passive"))
      (node (ref "C32") (pin "2") (pinfunction "2_2") (pintype "passive"))
      (node (ref "C35") (pin "2") (pinfunction "2_2") (pintype "passive"))
      (node (ref "C4") (pin "2") (pinfunction "2_2") (pintype "passive"))
      (node (ref "C43") (pin "2") (pinfunction "2_2") (pintype "passive"))
      (node (ref "C44") (pin "2") (pinfunction "2_2") (pintype "passive"))
      (node (ref "C45") (pin "2") (pinfunction "2_2") (pintype "passive"))
      (node (ref "C46") (pin "2") (pinfunction "2_2") (pintype "passive"))
      (node (ref "C47") (pin "2") (pinfunction "2_2") (pintype "passive"))
      (node (ref "C49") (pin "2") (pinfunction "2_2") (pintype "passive"))
      (node (ref "C5") (pin "2") (pinfunction "2_2") (pintype "passive"))
      (node (ref "C51") (pin "2") (pinfunction "2_2") (pintype "passive"))
      (node (ref "C52") (pin "2") (pinfunction "2_2") (pintype "passive"))
      (node (ref "C53") (pin "2") (pinfunction "2_2") (pintype "passive"))
      (node (ref "C54") (pin "2") (pinfunction "2_2") (pintype "passive"))
      (node (ref "C56") (pin "2") (pinfunction "2_2") (pintype "passive"))
      (node (ref "C6") (pin "2") (pinfunction "2_2") (pintype "passive"))
      (node (ref "C65") (pin "2") (pinfunction "2_2") (pintype "passive"))
      (node (ref "C68") (pin "2") (pinfunction "2_2") (pintype "passive"))
      (node (ref "C7") (pin "2") (pinfunction "2_2") (pintype "passive"))
      (node (ref "C8") (pin "2") (pinfunction "2_2") (pintype "passive"))
      (node (ref "C9") (pin "2") (pinfunction "2_2") (pintype "passive"))
      (node (ref "CC_DEBUG") (pin "1") (pinfunction "1_1") (pintype "bidirectional"))
      (node (ref "JTAG") (pin "3") (pinfunction "3_3") (pintype "bidirectional"))
      (node (ref "JTAG") (pin "5") (pinfunction "5_5") (pintype "bidirectional"))
      (node (ref "JTAG") (pin "9") (pinfunction "9_9") (pintype "bidirectional"))
      (node (ref "L10") (pin "1") (pinfunction "1_1") (pintype "passive"))
      (node (ref "MICROSD1") (pin "GND1") (pinfunction "GND_GND1") (pintype "bidirectional"))
      (node (ref "MICROSD1") (pin "GND2") (pinfunction "GND_GND2") (pintype "bidirectional"))
      (node (ref "MICROSD1") (pin "GND3") (pinfunction "GND_GND3") (pintype "bidirectional"))
      (node (ref "MICROSD1") (pin "GND4") (pinfunction "GND_GND4") (pintype "bidirectional"))
      (node (ref "MICROSD1") (pin "SWB") (pinfunction "SWB_SWB") (pintype "bidirectional"))
      (node (ref "MICROSD1") (pin "VSS") (pinfunction "GND_VSS") (pintype "bidirectional"))
      (node (ref "POWER") (pin "C") (pinfunction "C_C") (pintype "passive"))
      (node (ref "R10") (pin "1") (pinfunction "1_1") (pintype "passive"))
      (node (ref "R17") (pin "1") (pinfunction "1_1") (pintype "passive"))
      (node (ref "R20") (pin "1") (pinfunction "1_1") (pintype "passive"))
      (node (ref "R21") (pin "1") (pinfunction "1_1") (pintype "passive"))
      (node (ref "R32") (pin "1") (pinfunction "1_1") (pintype "passive"))
      (node (ref "R4") (pin "1") (pinfunction "1_1") (pintype "passive"))
      (node (ref "R8") (pin "1") (pinfunction "1_1") (pintype "passive"))
      (node (ref "RESET") (pin "3") (pinfunction "3_3") (pintype "bidirectional"))
      (node (ref "SMA") (pin "GND1") (pinfunction "GND_GND1") (pintype "bidirectional"))
      (node (ref "SMA") (pin "GND2") (pinfunction "GND_GND2") (pintype "bidirectional"))
      (node (ref "SMA") (pin "GND3") (pinfunction "GND_GND3") (pintype "bidirectional"))
      (node (ref "SMA") (pin "GND4") (pinfunction "GND_GND4") (pintype "bidirectional"))
      (node (ref "U1") (pin "29") (pinfunction "VBAT_29") (pintype "bidirectional"))
      (node (ref "U1") (pin "34") (pinfunction "GIO12_34") (pintype "bidirectional"))
      (node (ref "U1") (pin "35") (pinfunction "GIO13_35") (pintype "bidirectional"))
      (node (ref "U1") (pin "8") (pinfunction "GIO2_8") (pintype "bidirectional"))
      (node (ref "U1") (pin "GND") (pinfunction "GND_GND") (pintype "bidirectional"))
      (node (ref "U2") (pin "12") (pinfunction "GND_12") (pintype "bidirectional"))
      (node (ref "U2") (pin "14") (pinfunction "GND_14") (pintype "bidirectional"))
      (node (ref "U2") (pin "8") (pinfunction "GND_8") (pintype "bidirectional"))
      (node (ref "U2") (pin "9") (pinfunction "GND_9") (pintype "bidirectional"))
      (node (ref "U2") (pin "GND") (pinfunction "GND_GND") (pintype "bidirectional"))
      (node (ref "U3") (pin "28") (pinfunction "DVSS_28") (pintype "bidirectional"))
      (node (ref "U3") (pin "7") (pinfunction "IOVSS_7") (pintype "bidirectional"))
      (node (ref "U3") (pin "GND") (pinfunction "GND_GND") (pintype "bidirectional"))
      (node (ref "U5") (pin "2") (pinfunction "GND_2") (pintype "bidirectional"))
      (node (ref "U5") (pin "4") (pinfunction "GND_4") (pintype "bidirectional"))
      (node (ref "U6") (pin "1") (pinfunction "NTC_1") (pintype "bidirectional"))
      (node (ref "U6") (pin "14") (pinfunction "D1_14") (pintype "bidirectional"))
      (node (ref "U6") (pin "4") (pinfunction "D2_4") (pintype "bidirectional"))
      (node (ref "U6") (pin "GND") (pinfunction "GND_GND") (pintype "bidirectional"))
      (node (ref "U7") (pin "106") (pinfunction "GND_3_106") (pintype "bidirectional"))
      (node (ref "U7") (pin "12") (pinfunction "GND_1_12") (pintype "bidirectional"))
      (node (ref "U7") (pin "126") (pinfunction "GND_4_126") (pintype "bidirectional"))
      (node (ref "U7") (pin "33") (pinfunction "GNDPLL_33") (pintype "bidirectional"))
      (node (ref "U7") (pin "44") (pinfunction "GNDUTMI_44") (pintype "bidirectional"))
      (node (ref "U7") (pin "46") (pinfunction "JTAGSEL_46") (pintype "bidirectional"))
      (node (ref "U7") (pin "54") (pinfunction "GNDBU_54") (pintype "bidirectional"))
      (node (ref "U7") (pin "58") (pinfunction "GND_2_58") (pintype "bidirectional"))
      (node (ref "U7") (pin "74") (pinfunction "GNDANA_74") (pintype "bidirectional"))
      (node (ref "USB1") (pin "5") (pinfunction "GND_5") (pintype "bidirectional"))
      (node (ref "USB1") (pin "GND1") (pinfunction "GND_GND1") (pintype "bidirectional"))
      (node (ref "USB1") (pin "GND2") (pinfunction "GND_GND2") (pintype "bidirectional"))
      (node (ref "USB1") (pin "GND3") (pinfunction "GND_GND3") (pintype "bidirectional"))
      (node (ref "USB1") (pin "GND4") (pinfunction "GND_GND4") (pintype "bidirectional"))
      (node (ref "USB2") (pin "5") (pinfunction "GND_5") (pintype "bidirectional"))
      (node (ref "USB2") (pin "GND1") (pinfunction "GND_GND1") (pintype "bidirectional"))
      (node (ref "USB2") (pin "GND2") (pinfunction "GND_GND2") (pintype "bidirectional"))
      (node (ref "USB2") (pin "GND3") (pinfunction "GND_GND3") (pintype "bidirectional"))
      (node (ref "USB2") (pin "GND4") (pinfunction "GND_GND4") (pintype "bidirectional"))
      (node (ref "X1") (pin "2") (pinfunction "CASE_2") (pintype "passive"))
      (node (ref "X1") (pin "4") (pinfunction "CASE_4") (pintype "passive"))
      (node (ref "X3") (pin "GND-1") (pinfunction "CASE_GND-1") (pintype "passive"))
      (node (ref "X3") (pin "GND-2") (pinfunction "CASE_GND-2") (pintype "passive"))
    )
    (net (code "55") (name "GREEN_BOT") (class "Default")
      (node (ref "GREEN_BOT") (pin "2") (pinfunction "2_2") (pintype "passive"))
      (node (ref "U7") (pin "136") (pinfunction "PC25_136") (pintype "bidirectional"))
    )
    (net (code "56") (name "GREEN_TOP") (class "Default")
      (node (ref "GREEN_TOP") (pin "2") (pinfunction "2_2") (pintype "passive"))
      (node (ref "U7") (pin "133") (pinfunction "PC22_133") (pintype "bidirectional"))
    )
    (net (code "57") (name "IN_L") (class "Default")
      (node (ref "C38") (pin "1") (pinfunction "1_1") (pintype "passive"))
      (node (ref "LINE_IN") (pin "4") (pinfunction "L_4") (pintype "bidirectional"))
      (node (ref "R23") (pin "2") (pinfunction "2_2") (pintype "passive"))
    )
    (net (code "58") (name "IN_R") (class "Default")
      (node (ref "C37") (pin "1") (pinfunction "1_1") (pintype "passive"))
      (node (ref "LINE_IN") (pin "1") (pinfunction "R_1") (pintype "bidirectional"))
    )
    (net (code "59") (name "LINEIN_SENSE") (class "Default")
      (node (ref "LINEIN_SENSE") (pin "2") (pinfunction "2_2") (pintype "passive"))
      (node (ref "U7") (pin "101") (pinfunction "PC19_101") (pintype "bidirectional"))
    )
    (net (code "60") (name "LINE_L") (class "Default")
      (node (ref "LINE_L") (pin "1") (pinfunction "1_1") (pintype "passive"))
      (node (ref "U3") (pin "22") (pinfunction "LOL_22") (pintype "bidirectional"))
    )
    (net (code "61") (name "LINE_R") (class "Default")
      (node (ref "LINE_R") (pin "1") (pinfunction "1_1") (pintype "passive"))
      (node (ref "U3") (pin "23") (pinfunction "LOR_23") (pintype "bidirectional"))
    )
    (net (code "62") (name "LNA_EN") (class "Default")
      (node (ref "U1") (pin "38") (pinfunction "XLNAEN_38") (pintype "bidirectional"))
      (node (ref "U2") (pin "6") (pinfunction "EN_6") (pintype "bidirectional"))
    )
    (net (code "63") (name "MCLK") (class "Default")
      (node (ref "MCLK") (pin "2") (pinfunction "2_2") (pintype "passive"))
      (node (ref "U3") (pin "1") (pinfunction "MCLK_1") (pintype "bidirectional"))
    )
    (net (code "64") (name "MISO") (class "Default")
      (node (ref "MISO") (pin "2") (pinfunction "2_2") (pintype "passive"))
      (node (ref "MISO2") (pin "2") (pinfunction "2_2") (pintype "passive"))
      (node (ref "MISO3") (pin "2") (pinfunction "2_2") (pintype "passive"))
      (node (ref "MISO4") (pin "1") (pinfunction "1_1") (pintype "passive"))
      (node (ref "U7") (pin "108") (pinfunction "PA25_108") (pintype "bidirectional"))
    )
    (net (code "65") (name "MOSI") (class "Default")
      (node (ref "MOSI") (pin "2") (pinfunction "2_2") (pintype "passive"))
      (node (ref "MOSI2") (pin "2") (pinfunction "2_2") (pintype "passive"))
      (node (ref "MOSI3") (pin "2") (pinfunction "2_2") (pintype "passive"))
      (node (ref "MOSI4") (pin "1") (pinfunction "1_1") (pintype "passive"))
      (node (ref "U7") (pin "109") (pinfunction "PA26_109") (pintype "bidirectional"))
    )
    (net (code "66") (name "M_BCLK") (class "Default")
      (node (ref "BCLK2") (pin "2") (pinfunction "2_2") (pintype "passive"))
      (node (ref "U7") (pin "7") (pinfunction "PA14_7") (pintype "bidirectional"))
    )
    (net (code "67") (name "M_DIN{slash}S_DOUT") (class "Default")
      (node (ref "DIN2") (pin "2") (pinfunction "2_2") (pintype "passive"))
      (node (ref "U7") (pin "89") (pinfunction "PB18_89") (pintype "bidirectional"))
    )
    (net (code "68") (name "M_DOUT{slash}S_DIN") (class "Default")
      (node (ref "DOUT2") (pin "2") (pinfunction "2_2") (pintype "passive"))
      (node (ref "U7") (pin "78") (pinfunction "PA16_78") (pintype "bidirectional"))
    )
    (net (code "69") (name "M_WCLK") (class "Default")
      (node (ref "U7") (pin "8") (pinfunction "PA15_8") (pintype "bidirectional"))
      (node (ref "WCLK2") (pin "2") (pinfunction "2_2") (pintype "passive"))
    )
    (net (code "70") (name "Net-(!SD_CARD-Pad2)") (class "Default")
      (node (ref "!SD_CARD") (pin "2") (pinfunction "2_2") (pintype "passive"))
      (node (ref "MICROSD1") (pin "SWA") (pinfunction "SWA_SWA") (pintype "bidirectional"))
    )
    (net (code "71") (name "Net-(AMP_VDD-Pad1)") (class "Default")
      (node (ref "AMP_VDD") (pin "1") (pinfunction "1_1") (pintype "passive"))
      (node (ref "L3") (pin "2") (pinfunction "2_2") (pintype "passive"))
    )
    (net (code "72") (name "Net-(AUX_VDD-Pad1)") (class "Default")
      (node (ref "AUX_VDD") (pin "1") (pinfunction "1_1") (pintype "passive"))
      (node (ref "L18") (pin "2") (pinfunction "2_2") (pintype "passive"))
    )
    (net (code "73") (name "Net-(AVDD-Pad1)") (class "Default")
      (node (ref "AVDD") (pin "1") (pinfunction "1_1") (pintype "passive"))
      (node (ref "L2") (pin "2") (pinfunction "2_2") (pintype "passive"))
    )
    (net (code "74") (name "Net-(AVDD_CODEC-Pad1)") (class "Default")
      (node (ref "AVDD_CODEC") (pin "1") (pinfunction "1_1") (pintype "passive"))
      (node (ref "L14") (pin "2") (pinfunction "2_2") (pintype "passive"))
    )
    (net (code "75") (name "Net-(AVR-PadA)") (class "Default")
      (node (ref "AVR") (pin "A") (pinfunction "A_A") (pintype "passive"))
      (node (ref "R44") (pin "1") (pinfunction "1_1") (pintype "passive"))
    )
    (net (code "76") (name "Net-(AVR1-PadA)") (class "Default")
      (node (ref "AVR1") (pin "A") (pinfunction "A_A") (pintype "passive"))
      (node (ref "R6") (pin "1") (pinfunction "1_1") (pintype "passive"))
    )
    (net (code "77") (name "Net-(AVR2-PadA)") (class "Default")
      (node (ref "AVR2") (pin "A") (pinfunction "A_A") (pintype "passive"))
      (node (ref "R27") (pin "1") (pinfunction "1_1") (pintype "passive"))
    )
    (net (code "78") (name "Net-(AVR_VDD-Pad1)") (class "Default")
      (node (ref "AVR_VDD") (pin "1") (pinfunction "1_1") (pintype "passive"))
      (node (ref "L16") (pin "2") (pinfunction "2_2") (pintype "passive"))
    )
    (net (code "79") (name "Net-(BATTERY-P)") (class "Default")
      (node (ref "BATTERY") (pin "+") (pinfunction "P_+") (pintype "passive"))
      (node (ref "Q1") (pin "2") (pinfunction "S_2") (pintype "passive"))
      (node (ref "U6") (pin "9") (pinfunction "BAT_9") (pintype "bidirectional"))
    )
    (net (code "80") (name "Net-(C25-Pad1)") (class "Default")
      (node (ref "C25") (pin "1") (pinfunction "1_1") (pintype "passive"))
      (node (ref "L8") (pin "2") (pinfunction "2_2") (pintype "passive"))
    )
    (net (code "81") (name "Net-(C25-Pad2)") (class "Default")
      (node (ref "C25") (pin "2") (pinfunction "2_2") (pintype "passive"))
      (node (ref "C26") (pin "1") (pinfunction "1_1") (pintype "passive"))
      (node (ref "C28") (pin "1") (pinfunction "1_1") (pintype "passive"))
      (node (ref "L10") (pin "2") (pinfunction "2_2") (pintype "passive"))
    )
    (net (code "82") (name "Net-(C26-Pad2)") (class "Default")
      (node (ref "C26") (pin "2") (pinfunction "2_2") (pintype "passive"))
      (node (ref "SMA") (pin "SIG") (pinfunction "SIG_SIG") (pintype "bidirectional"))
    )
    (net (code "83") (name "Net-(C27-Pad1)") (class "Default")
      (node (ref "C27") (pin "1") (pinfunction "1_1") (pintype "passive"))
      (node (ref "L7") (pin "2") (pinfunction "2_2") (pintype "passive"))
      (node (ref "L8") (pin "1") (pinfunction "1_1") (pintype "passive"))
    )
    (net (code "84") (name "Net-(C54-Pad1)") (class "Default")
      (node (ref "C54") (pin "1") (pinfunction "1_1") (pintype "passive"))
      (node (ref "R19") (pin "1") (pinfunction "1_1") (pintype "passive"))
    )
    (net (code "85") (name "Net-(CC8531-PadC)") (class "Default")
      (node (ref "CC8531") (pin "C") (pinfunction "C_C") (pintype "passive"))
      (node (ref "R5") (pin "2") (pinfunction "2_2") (pintype "passive"))
    )
    (net (code "86") (name "Net-(CC_DEBUG-Pad9)") (class "Default")
      (node (ref "CC_DEBUG") (pin "9") (pinfunction "9_9") (pintype "bidirectional"))
      (node (ref "EXT") (pin "2") (pinfunction "2_2") (pintype "passive"))
    )
    (net (code "87") (name "Net-(CHARGE-PadA)") (class "Default")
      (node (ref "CHARGE") (pin "A") (pinfunction "A_A") (pintype "passive"))
      (node (ref "R18") (pin "1") (pinfunction "1_1") (pintype "passive"))
    )
    (net (code "88") (name "Net-(DVDD_CODEC-Pad1)") (class "Default")
      (node (ref "DVDD_CODEC") (pin "1") (pinfunction "1_1") (pintype "passive"))
      (node (ref "L15") (pin "2") (pinfunction "2_2") (pintype "passive"))
    )
    (net (code "89") (name "Net-(IOVDD-Pad1)") (class "Default")
      (node (ref "IOVDD") (pin "1") (pinfunction "1_1") (pintype "passive"))
      (node (ref "L1") (pin "2") (pinfunction "2_2") (pintype "passive"))
    )
    (net (code "90") (name "Net-(LINE_L-Pad2)") (class "Default")
      (node (ref "LINE_L") (pin "2") (pinfunction "2_2") (pintype "passive"))
      (node (ref "PHONE_L") (pin "2") (pinfunction "2_2") (pintype "passive"))
      (node (ref "R13") (pin "2") (pinfunction "2_2") (pintype "passive"))
    )
    (net (code "91") (name "Net-(LINE_R-Pad2)") (class "Default")
      (node (ref "LINE_R") (pin "2") (pinfunction "2_2") (pintype "passive"))
      (node (ref "PHONE_R") (pin "2") (pinfunction "2_2") (pintype "passive"))
      (node (ref "R16") (pin "2") (pinfunction "2_2") (pintype "passive"))
    )
    (net (code "92") (name "Net-(MICROSD1-MISO)") (class "Default")
      (node (ref "MICROSD1") (pin "DAT0") (pinfunction "MISO_DAT0") (pintype "bidirectional"))
      (node (ref "MISO4") (pin "2") (pinfunction "2_2") (pintype "passive"))
    )
    (net (code "93") (name "Net-(MICROSD1-MOSI)") (class "Default")
      (node (ref "MICROSD1") (pin "CMD") (pinfunction "MOSI_CMD") (pintype "bidirectional"))
      (node (ref "MOSI4") (pin "2") (pinfunction "2_2") (pintype "passive"))
    )
    (net (code "94") (name "Net-(MICROSD1-PadVDD)") (class "Default")
      (node (ref "MICROSD1") (pin "VDD") (pinfunction "VDD_VDD") (pintype "bidirectional"))
      (node (ref "VDD_SD") (pin "1") (pinfunction "1_1") (pintype "passive"))
    )
    (net (code "95") (name "Net-(MICROSD1-SCLK)") (class "Default")
      (node (ref "MICROSD1") (pin "CLK") (pinfunction "SCLK_CLK") (pintype "bidirectional"))
      (node (ref "SCLK4") (pin "2") (pinfunction "2_2") (pintype "passive"))
    )
    (net (code "96") (name "Net-(MICROSD1-~{CS})") (class "Default")
      (node (ref "CS_SD") (pin "2") (pinfunction "2_2") (pintype "passive"))
      (node (ref "MICROSD1") (pin "CD/DAT3") (pinfunction "~{CS}_CD/DAT3") (pintype "bidirectional"))
    )
    (net (code "97") (name "Net-(POWER-PadA)") (class "Default")
      (node (ref "POWER") (pin "A") (pinfunction "A_A") (pintype "passive"))
      (node (ref "R3") (pin "1") (pinfunction "1_1") (pintype "passive"))
    )
    (net (code "98") (name "Net-(Q1-D)") (class "Default")
      (node (ref "C52") (pin "1") (pinfunction "1_1") (pintype "passive"))
      (node (ref "F1") (pin "1") (pinfunction "1_1") (pintype "passive"))
      (node (ref "L17") (pin "2") (pinfunction "2_2") (pintype "passive"))
      (node (ref "Q1") (pin "3") (pinfunction "D_3") (pintype "passive"))
      (node (ref "U6") (pin "10") (pinfunction "VOUT_10") (pintype "bidirectional"))
      (node (ref "U6") (pin "3") (pinfunction "VOUTS_3") (pintype "bidirectional"))
    )
    (net (code "99") (name "Net-(Q1-G)") (class "Default")
      (node (ref "Q1") (pin "1") (pinfunction "G_1") (pintype "passive"))
      (node (ref "U6") (pin "8") (pinfunction "GATE_8") (pintype "bidirectional"))
    )
    (net (code "100") (name "Net-(Q2-D)") (class "Default")
      (node (ref "LED_UL") (pin "1") (pinfunction "KR_1") (pintype "passive"))
      (node (ref "LED_UL") (pin "1-2") (pinfunction "KR_1-2") (pintype "passive"))
      (node (ref "LED_UR") (pin "1") (pinfunction "KR_1") (pintype "passive"))
      (node (ref "LED_UR") (pin "1-2") (pinfunction "KR_1-2") (pintype "passive"))
      (node (ref "Q2") (pin "3") (pinfunction "D_3") (pintype "passive"))
    )
    (net (code "101") (name "Net-(Q3-D)") (class "Default")
      (node (ref "LED_UL") (pin "4") (pinfunction "KG_4") (pintype "passive"))
      (node (ref "LED_UL") (pin "4-2") (pinfunction "KG_4-2") (pintype "passive"))
      (node (ref "LED_UR") (pin "4") (pinfunction "KG_4") (pintype "passive"))
      (node (ref "LED_UR") (pin "4-2") (pinfunction "KG_4-2") (pintype "passive"))
      (node (ref "Q3") (pin "3") (pinfunction "D_3") (pintype "passive"))
    )
    (net (code "102") (name "Net-(Q4-D)") (class "Default")
      (node (ref "LED_UL") (pin "3") (pinfunction "KB_3") (pintype "passive"))
      (node (ref "LED_UL") (pin "3-2") (pinfunction "KB_3-2") (pintype "passive"))
      (node (ref "LED_UR") (pin "3") (pinfunction "KB_3") (pintype "passive"))
      (node (ref "LED_UR") (pin "3-2") (pinfunction "KB_3-2") (pintype "passive"))
      (node (ref "Q4") (pin "3") (pinfunction "D_3") (pintype "passive"))
    )
    (net (code "103") (name "Net-(Q5-D)") (class "Default")
      (node (ref "LED_LL") (pin "1") (pinfunction "KR_1") (pintype "passive"))
      (node (ref "LED_LL") (pin "1-2") (pinfunction "KR_1-2") (pintype "passive"))
      (node (ref "LED_LR") (pin "1") (pinfunction "KR_1") (pintype "passive"))
      (node (ref "LED_LR") (pin "1-2") (pinfunction "KR_1-2") (pintype "passive"))
      (node (ref "Q5") (pin "3") (pinfunction "D_3") (pintype "passive"))
    )
    (net (code "104") (name "Net-(Q6-D)") (class "Default")
      (node (ref "LED_LL") (pin "4") (pinfunction "KG_4") (pintype "passive"))
      (node (ref "LED_LL") (pin "4-2") (pinfunction "KG_4-2") (pintype "passive"))
      (node (ref "LED_LR") (pin "4") (pinfunction "KG_4") (pintype "passive"))
      (node (ref "LED_LR") (pin "4-2") (pinfunction "KG_4-2") (pintype "passive"))
      (node (ref "Q6") (pin "3") (pinfunction "D_3") (pintype "passive"))
    )
    (net (code "105") (name "Net-(Q7-D)") (class "Default")
      (node (ref "LED_LL") (pin "3") (pinfunction "KB_3") (pintype "passive"))
      (node (ref "LED_LL") (pin "3-2") (pinfunction "KB_3-2") (pintype "passive"))
      (node (ref "LED_LR") (pin "3") (pinfunction "KB_3") (pintype "passive"))
      (node (ref "LED_LR") (pin "3-2") (pinfunction "KB_3-2") (pintype "passive"))
      (node (ref "Q7") (pin "3") (pinfunction "D_3") (pintype "passive"))
    )
    (net (code "106") (name "Net-(R26-Pad2)") (class "Default")
      (node (ref "R26") (pin "2") (pinfunction "2_2") (pintype "passive"))
      (node (ref "SW1") (pin "P$1") (pinfunction "P$1_P$1") (pintype "bidirectional"))
    )
    (net (code "107") (name "Net-(R33-Pad2)") (class "Default")
      (node (ref "R33") (pin "2") (pinfunction "2_2") (pintype "passive"))
      (node (ref "SW4") (pin "P$1") (pinfunction "P$1_P$1") (pintype "bidirectional"))
    )
    (net (code "108") (name "Net-(R34-Pad2)") (class "Default")
      (node (ref "R34") (pin "2") (pinfunction "2_2") (pintype "passive"))
      (node (ref "SW5") (pin "P$1") (pinfunction "P$1_P$1") (pintype "bidirectional"))
    )
    (net (code "109") (name "Net-(R35-Pad2)") (class "Default")
      (node (ref "R35") (pin "2") (pinfunction "2_2") (pintype "passive"))
      (node (ref "SW6") (pin "P$1") (pinfunction "P$1_P$1") (pintype "bidirectional"))
    )
    (net (code "110") (name "Net-(R37-Pad2)") (class "Default")
      (node (ref "R37") (pin "2") (pinfunction "2_2") (pintype "passive"))
      (node (ref "SW7") (pin "P$1") (pinfunction "P$1_P$1") (pintype "bidirectional"))
    )
    (net (code "111") (name "Net-(R38-Pad2)") (class "Default")
      (node (ref "R38") (pin "2") (pinfunction "2_2") (pintype "passive"))
      (node (ref "SW8") (pin "P$1") (pinfunction "P$1_P$1") (pintype "bidirectional"))
    )
    (net (code "112") (name "Net-(R39-Pad2)") (class "Default")
      (node (ref "R39") (pin "2") (pinfunction "2_2") (pintype "passive"))
      (node (ref "SW9") (pin "P$1") (pinfunction "P$1_P$1") (pintype "bidirectional"))
    )
    (net (code "113") (name "Net-(R40-Pad2)") (class "Default")
      (node (ref "R40") (pin "2") (pinfunction "2_2") (pintype "passive"))
      (node (ref "SW10") (pin "P$1") (pinfunction "P$1_P$1") (pintype "bidirectional"))
    )
    (net (code "114") (name "Net-(U1-AD0{slash}GIO7)") (class "Default")
      (node (ref "L11") (pin "2") (pinfunction "2_2") (pintype "passive"))
      (node (ref "U1") (pin "16") (pinfunction "AD0/GIO7_16") (pintype "bidirectional"))
    )
    (net (code "115") (name "Net-(U1-AD1{slash}GIO8)") (class "Default")
      (node (ref "L13") (pin "2") (pinfunction "2_2") (pintype "passive"))
      (node (ref "U1") (pin "17") (pinfunction "AD1/GIO8_17") (pintype "bidirectional"))
    )
    (net (code "116") (name "Net-(U1-BCLK{slash}GIO5)") (class "Default")
      (node (ref "L6") (pin "2") (pinfunction "2_2") (pintype "passive"))
      (node (ref "U1") (pin "14") (pinfunction "BCLK/GIO5_14") (pintype "bidirectional"))
    )
    (net (code "117") (name "Net-(U1-DCPL)") (class "Default")
      (node (ref "C23") (pin "1") (pinfunction "1_1") (pintype "passive"))
      (node (ref "U1") (pin "39") (pinfunction "DCPL_39") (pintype "bidirectional"))
    )
    (net (code "118") (name "Net-(U1-GIO3)") (class "Default")
      (node (ref "R5") (pin "1") (pinfunction "1_1") (pintype "passive"))
      (node (ref "U1") (pin "9") (pinfunction "GIO3_9") (pintype "bidirectional"))
    )
    (net (code "119") (name "Net-(U1-MCLK{slash}GIO4)") (class "Default")
      (node (ref "L5") (pin "2") (pinfunction "2_2") (pintype "passive"))
      (node (ref "U1") (pin "13") (pinfunction "MCLK/GIO4_13") (pintype "bidirectional"))
    )
    (net (code "120") (name "Net-(U1-RBIAS)") (class "Default")
      (node (ref "R4") (pin "2") (pinfunction "2_2") (pintype "passive"))
      (node (ref "U1") (pin "30") (pinfunction "RBIAS_30") (pintype "bidirectional"))
    )
    (net (code "121") (name "Net-(U1-RSTN)") (class "Default")
      (node (ref "L4") (pin "1") (pinfunction "1_1") (pintype "passive"))
      (node (ref "U1") (pin "11") (pinfunction "RSTN_11") (pintype "bidirectional"))
    )
    (net (code "122") (name "Net-(U1-USBN)") (class "Default")
      (node (ref "C14") (pin "1") (pinfunction "1_1") (pintype "passive"))
      (node (ref "R1") (pin "1") (pinfunction "1_1") (pintype "passive"))
      (node (ref "U1") (pin "1") (pinfunction "USBN_1") (pintype "bidirectional"))
    )
    (net (code "123") (name "Net-(U1-USBP)") (class "Default")
      (node (ref "C13") (pin "1") (pinfunction "1_1") (pintype "passive"))
      (node (ref "R2") (pin "1") (pinfunction "1_1") (pintype "passive"))
      (node (ref "U1") (pin "2") (pinfunction "USBP_2") (pintype "bidirectional"))
    )
    (net (code "124") (name "Net-(U1-WCLK{slash}GIO6)") (class "Default")
      (node (ref "L9") (pin "2") (pinfunction "2_2") (pintype "passive"))
      (node (ref "U1") (pin "15") (pinfunction "WCLK/GIO6_15") (pintype "bidirectional"))
    )
    (net (code "125") (name "Net-(U1-X0)") (class "Default")
      (node (ref "C24") (pin "1") (pinfunction "1_1") (pintype "passive"))
      (node (ref "U1") (pin "22") (pinfunction "X0_22") (pintype "bidirectional"))
      (node (ref "X1") (pin "3") (pinfunction "2_3") (pintype "passive"))
    )
    (net (code "126") (name "Net-(U1-X1)") (class "Default")
      (node (ref "C29") (pin "1") (pinfunction "1_1") (pintype "passive"))
      (node (ref "U1") (pin "21") (pinfunction "X1_21") (pintype "bidirectional"))
      (node (ref "X1") (pin "1") (pinfunction "1_1") (pintype "passive"))
    )
    (net (code "127") (name "Net-(U1-XPAEN)") (class "Default")
      (node (ref "L12") (pin "1") (pinfunction "1_1") (pintype "passive"))
      (node (ref "U1") (pin "36") (pinfunction "XPAEN_36") (pintype "bidirectional"))
    )
    (net (code "128") (name "Net-(U2-ANT)") (class "Default")
      (node (ref "L7") (pin "1") (pinfunction "1_1") (pintype "passive"))
      (node (ref "U2") (pin "11") (pinfunction "ANT_11") (pintype "bidirectional"))
    )
    (net (code "129") (name "Net-(U2-BIAS)") (class "Default")
      (node (ref "R8") (pin "2") (pinfunction "2_2") (pintype "passive"))
      (node (ref "U2") (pin "15") (pinfunction "BIAS_15") (pintype "bidirectional"))
    )
    (net (code "130") (name "Net-(U2-HGM)") (class "Default")
      (node (ref "R9") (pin "1") (pinfunction "1_1") (pintype "passive"))
      (node (ref "U2") (pin "7") (pinfunction "HGM_7") (pintype "bidirectional"))
    )
    (net (code "131") (name "Net-(U3-AVDD)") (class "Default")
      (node (ref "C48") (pin "1") (pinfunction "1_1") (pintype "passive"))
      (node (ref "U3") (pin "24") (pinfunction "AVDD_24") (pintype "bidirectional"))
    )
    (net (code "132") (name "Net-(U3-DVDD)") (class "Default")
      (node (ref "C49") (pin "1") (pinfunction "1_1") (pintype "passive"))
      (node (ref "U3") (pin "29") (pinfunction "DVDD_29") (pintype "bidirectional"))
    )
    (net (code "133") (name "Net-(U3-IN1_L)") (class "Default")
      (node (ref "C38") (pin "2") (pinfunction "2_2") (pintype "passive"))
      (node (ref "U3") (pin "13") (pinfunction "IN1_L_13") (pintype "bidirectional"))
    )
    (net (code "134") (name "Net-(U3-IN1_R)") (class "Default")
      (node (ref "C37") (pin "2") (pinfunction "2_2") (pintype "passive"))
      (node (ref "U3") (pin "14") (pinfunction "IN1_R_14") (pintype "bidirectional"))
    )
    (net (code "135") (name "Net-(U3-REF)") (class "Default")
      (node (ref "C50") (pin "1") (pinfunction "1_1") (pintype "passive"))
      (node (ref "U3") (pin "18") (pinfunction "REF_18") (pintype "bidirectional"))
    )
    (net (code "136") (name "Net-(U5-VIN)") (class "Default")
      (node (ref "F1") (pin "2") (pinfunction "2_2") (pintype "passive"))
      (node (ref "U5") (pin "1") (pinfunction "VIN_1") (pintype "bidirectional"))
    )
    (net (code "137") (name "Net-(U6-CLRPROG)") (class "Default")
      (node (ref "R19") (pin "2") (pinfunction "2_2") (pintype "passive"))
      (node (ref "R20") (pin "2") (pinfunction "2_2") (pintype "passive"))
      (node (ref "U6") (pin "2") (pinfunction "CLRPROG_2") (pintype "bidirectional"))
    )
    (net (code "138") (name "Net-(U6-C{slash}X)") (class "Default")
      (node (ref "R21") (pin "2") (pinfunction "2_2") (pintype "passive"))
      (node (ref "U6") (pin "5") (pinfunction "C/X_5") (pintype "bidirectional"))
      (node (ref "U6") (pin "6") (pinfunction "PROG_6") (pintype "bidirectional"))
    )
    (net (code "139") (name "Net-(U6-SW)") (class "Default")
      (node (ref "L17") (pin "1") (pinfunction "1_1") (pintype "passive"))
      (node (ref "U6") (pin "12") (pinfunction "SW_12") (pintype "bidirectional"))
    )
    (net (code "140") (name "Net-(U6-~{CHRG})") (class "Default")
      (node (ref "CHARGE") (pin "C") (pinfunction "C_C") (pintype "passive"))
      (node (ref "U6") (pin "7") (pinfunction "~{CHRG}_7") (pintype "bidirectional"))
    )
    (net (code "141") (name "Net-(U7F-DFSDM)") (class "Default")
      (node (ref "R41") (pin "1") (pinfunction "1_1") (pintype "passive"))
      (node (ref "U7") (pin "43") (pinfunction "DFSDM_43") (pintype "bidirectional"))
    )
    (net (code "142") (name "Net-(U7F-DFSDP)") (class "Default")
      (node (ref "R42") (pin "1") (pinfunction "1_1") (pintype "passive"))
      (node (ref "U7") (pin "42") (pinfunction "DFSDP_42") (pintype "bidirectional"))
    )
    (net (code "143") (name "Net-(U7F-FWUP)") (class "Default")
      (node (ref "R43") (pin "2") (pinfunction "2_2") (pintype "passive"))
      (node (ref "U7") (pin "53") (pinfunction "FWUP_53") (pintype "bidirectional"))
    )
    (net (code "144") (name "Net-(U7F-VBG)") (class "Default")
      (node (ref "C68") (pin "1") (pinfunction "1_1") (pintype "passive"))
      (node (ref "R32") (pin "2") (pinfunction "2_2") (pintype "passive"))
      (node (ref "U7") (pin "40") (pinfunction "VBG_40") (pintype "bidirectional"))
    )
    (net (code "145") (name "Net-(U7F-XIN)") (class "Default")
      (node (ref "C30") (pin "1") (pinfunction "1_1") (pintype "passive"))
      (node (ref "U7") (pin "36") (pinfunction "XIN_36") (pintype "bidirectional"))
      (node (ref "X3") (pin "X2") (pinfunction "2_X2") (pintype "passive"))
    )
    (net (code "146") (name "Net-(U7F-XOUT)") (class "Default")
      (node (ref "C56") (pin "1") (pinfunction "1_1") (pintype "passive"))
      (node (ref "U7") (pin "35") (pinfunction "XOUT_35") (pintype "bidirectional"))
      (node (ref "X3") (pin "X1") (pinfunction "1_X1") (pintype "passive"))
    )
    (net (code "147") (name "Net-(U8-SNS3)") (class "Default")
      (node (ref "C58") (pin "1") (pinfunction "1_1") (pintype "passive"))
      (node (ref "U8") (pin "8") (pinfunction "SNS3_8") (pintype "bidirectional"))
    )
    (net (code "148") (name "Net-(U8-SNS3K)") (class "Default")
      (node (ref "C58") (pin "2") (pinfunction "2_2") (pintype "passive"))
      (node (ref "R33") (pin "1") (pinfunction "1_1") (pintype "passive"))
      (node (ref "U8") (pin "9") (pinfunction "SNS3K_9") (pintype "bidirectional"))
    )
    (net (code "149") (name "Net-(U8-SNS4)") (class "Default")
      (node (ref "C59") (pin "1") (pinfunction "1_1") (pintype "passive"))
      (node (ref "U8") (pin "10") (pinfunction "SNS4_10") (pintype "bidirectional"))
    )
    (net (code "150") (name "Net-(U8-SNS4K)") (class "Default")
      (node (ref "C59") (pin "2") (pinfunction "2_2") (pintype "passive"))
      (node (ref "R34") (pin "1") (pinfunction "1_1") (pintype "passive"))
      (node (ref "U8") (pin "11") (pinfunction "SNS4K_11") (pintype "bidirectional"))
    )
    (net (code "151") (name "Net-(U8-SNS5)") (class "Default")
      (node (ref "C60") (pin "1") (pinfunction "1_1") (pintype "passive"))
      (node (ref "U8") (pin "12") (pinfunction "SNS5_12") (pintype "bidirectional"))
    )
    (net (code "152") (name "Net-(U8-SNS5K)") (class "Default")
      (node (ref "C60") (pin "2") (pinfunction "2_2") (pintype "passive"))
      (node (ref "R35") (pin "1") (pinfunction "1_1") (pintype "passive"))
      (node (ref "U8") (pin "13") (pinfunction "SNS5K_13") (pintype "bidirectional"))
    )
    (net (code "153") (name "Net-(U8-SNS6)") (class "Default")
      (node (ref "C61") (pin "1") (pinfunction "1_1") (pintype "passive"))
      (node (ref "U8") (pin "20") (pinfunction "SNS6_20") (pintype "bidirectional"))
    )
    (net (code "154") (name "Net-(U8-SNS6K)") (class "Default")
      (node (ref "C61") (pin "2") (pinfunction "2_2") (pintype "passive"))
      (node (ref "R37") (pin "1") (pinfunction "1_1") (pintype "passive"))
      (node (ref "U8") (pin "19") (pinfunction "SNS6K_19") (pintype "bidirectional"))
    )
    (net (code "155") (name "Net-(U8-SNS7K{slash}DETECT0)") (class "Default")
      (node (ref "C62") (pin "2") (pinfunction "2_2") (pintype "passive"))
      (node (ref "R38") (pin "1") (pinfunction "1_1") (pintype "passive"))
      (node (ref "U8") (pin "22") (pinfunction "SNS7K/DETECT0_22") (pintype "bidirectional"))
    )
    (net (code "156") (name "Net-(U8-SNS7{slash}DETECT1)") (class "Default")
      (node (ref "C62") (pin "1") (pinfunction "1_1") (pintype "passive"))
      (node (ref "U8") (pin "23") (pinfunction "SNS7/DETECT1_23") (pintype "bidirectional"))
    )
    (net (code "157") (name "Net-(U8-SNS8K{slash}DETECT3)") (class "Default")
      (node (ref "C66") (pin "2") (pinfunction "2_2") (pintype "passive"))
      (node (ref "R39") (pin "1") (pinfunction "1_1") (pintype "passive"))
      (node (ref "U8") (pin "25") (pinfunction "SNS8K/DETECT3_25") (pintype "bidirectional"))
    )
    (net (code "158") (name "Net-(U8-SNS8{slash}DETECT2)") (class "Default")
      (node (ref "C66") (pin "1") (pinfunction "1_1") (pintype "passive"))
      (node (ref "U8") (pin "24") (pinfunction "SNS8/DETECT2_24") (pintype "bidirectional"))
    )
    (net (code "159") (name "Net-(U8-SNS9K{slash}DETECT5)") (class "Default")
      (node (ref "C67") (pin "2") (pinfunction "2_2") (pintype "passive"))
      (node (ref "R40") (pin "1") (pinfunction "1_1") (pintype "passive"))
      (node (ref "U8") (pin "27") (pinfunction "SNS9K/DETECT5_27") (pintype "bidirectional"))
    )
    (net (code "160") (name "Net-(U8-SNS9{slash}DETECT4)") (class "Default")
      (node (ref "C67") (pin "1") (pinfunction "1_1") (pintype "passive"))
      (node (ref "U8") (pin "26") (pinfunction "SNS9/DETECT4_26") (pintype "bidirectional"))
    )
    (net (code "161") (name "Net-(U8-SNS10K{slash}SYNC)") (class "Default")
      (node (ref "C55") (pin "2") (pinfunction "2_2") (pintype "passive"))
      (node (ref "R26") (pin "1") (pinfunction "1_1") (pintype "passive"))
      (node (ref "U8") (pin "31") (pinfunction "SNS10K/SYNC_31") (pintype "bidirectional"))
    )
    (net (code "162") (name "Net-(U8-SNS10{slash}DETECT16)") (class "Default")
      (node (ref "C55") (pin "1") (pinfunction "1_1") (pintype "passive"))
      (node (ref "U8") (pin "30") (pinfunction "SNS10/DETECT16_30") (pintype "bidirectional"))
    )
    (net (code "163") (name "Net-(U8-~{RESET})") (class "Default")
      (node (ref "R36") (pin "1") (pinfunction "1_1") (pintype "passive"))
      (node (ref "U8") (pin "29") (pinfunction "~{RESET}_29") (pintype "bidirectional"))
    )
    (net (code "164") (name "Net-(U9-BYPASS)") (class "Default")
      (node (ref "C33") (pin "1") (pinfunction "1_1") (pintype "passive"))
      (node (ref "U9") (pin "1") (pinfunction "BYPASS_1") (pintype "bidirectional"))
    )
    (net (code "165") (name "Net-(U9-INA)") (class "Default")
      (node (ref "R12") (pin "2") (pinfunction "2_2") (pintype "passive"))
      (node (ref "R13") (pin "1") (pinfunction "1_1") (pintype "passive"))
      (node (ref "U9") (pin "8") (pinfunction "INA_8") (pintype "bidirectional"))
    )
    (net (code "166") (name "Net-(U9-INB)") (class "Default")
      (node (ref "R15") (pin "2") (pinfunction "2_2") (pintype "passive"))
      (node (ref "R16") (pin "1") (pinfunction "1_1") (pintype "passive"))
      (node (ref "U9") (pin "4") (pinfunction "INB_4") (pintype "bidirectional"))
    )
    (net (code "167") (name "Net-(U9-OUTB)") (class "Default")
      (node (ref "C39") (pin "1") (pinfunction "1_1") (pintype "passive"))
      (node (ref "R15") (pin "1") (pinfunction "1_1") (pintype "passive"))
      (node (ref "U9") (pin "5") (pinfunction "OUTB_5") (pintype "bidirectional"))
    )
    (net (code "168") (name "Net-(U9-SHUTDOWN)") (class "Default")
      (node (ref "R31") (pin "1") (pinfunction "1_1") (pintype "passive"))
      (node (ref "U9") (pin "3") (pinfunction "SHUTDOWN_3") (pintype "bidirectional"))
    )
    (net (code "169") (name "OUT_L") (class "Default")
      (node (ref "C36") (pin "2") (pinfunction "2_2") (pintype "passive"))
      (node (ref "PHONE_OUT") (pin "4") (pinfunction "L_4") (pintype "bidirectional"))
      (node (ref "R25") (pin "2") (pinfunction "2_2") (pintype "passive"))
    )
    (net (code "170") (name "OUT_R") (class "Default")
      (node (ref "C39") (pin "2") (pinfunction "2_2") (pintype "passive"))
      (node (ref "PHONE_OUT") (pin "1") (pinfunction "R_1") (pintype "bidirectional"))
    )
    (net (code "171") (name "PA_EN") (class "Default")
      (node (ref "L12") (pin "2") (pinfunction "2_2") (pintype "passive"))
      (node (ref "R10") (pin "2") (pinfunction "2_2") (pintype "passive"))
      (node (ref "U2") (pin "5") (pinfunction "PAEN_5") (pintype "bidirectional"))
    )
    (net (code "172") (name "PHONE_L") (class "Default")
      (node (ref "PHONE_L") (pin "1") (pinfunction "1_1") (pintype "passive"))
      (node (ref "U3") (pin "25") (pinfunction "HPL_25") (pintype "bidirectional"))
    )
    (net (code "173") (name "PHONE_R") (class "Default")
      (node (ref "PHONE_R") (pin "1") (pinfunction "1_1") (pintype "passive"))
      (node (ref "U3") (pin "27") (pinfunction "HPR_27") (pintype "bidirectional"))
    )
    (net (code "174") (name "PHONE_SENSE") (class "Default")
      (node (ref "PHONE_SENSE") (pin "2") (pinfunction "2_2") (pintype "passive"))
      (node (ref "U7") (pin "140") (pinfunction "PB14_140") (pintype "bidirectional"))
    )
    (net (code "175") (name "RED_BOT") (class "Default")
      (node (ref "RED_BOT") (pin "2") (pinfunction "2_2") (pintype "passive"))
      (node (ref "U7") (pin "139") (pinfunction "PC28_139") (pintype "bidirectional"))
    )
    (net (code "176") (name "RED_TOP") (class "Default")
      (node (ref "RED_TOP") (pin "2") (pinfunction "2_2") (pintype "passive"))
      (node (ref "U7") (pin "132") (pinfunction "PC21_132") (pintype "bidirectional"))
    )
    (net (code "177") (name "RESET_CC8531") (class "Default")
      (node (ref "RESET_CC8531") (pin "2") (pinfunction "2_2") (pintype "passive"))
      (node (ref "U7") (pin "20") (pinfunction "PD7_20") (pintype "bidirectional"))
    )
    (net (code "178") (name "RESET_CODEC") (class "Default")
      (node (ref "RESET_CODEC") (pin "2") (pinfunction "2_2") (pintype "passive"))
      (node (ref "U7") (pin "16") (pinfunction "PD3_16") (pintype "bidirectional"))
    )
    (net (code "179") (name "RF_N") (class "Default")
      (node (ref "U1") (pin "25") (pinfunction "RF_N_25") (pintype "bidirectional"))
      (node (ref "U2") (pin "2") (pinfunction "RF_N_2") (pintype "bidirectional"))
    )
    (net (code "180") (name "RF_P") (class "Default")
      (node (ref "U1") (pin "24") (pinfunction "RF_P_24") (pintype "bidirectional"))
      (node (ref "U2") (pin "4") (pinfunction "RF_P_4") (pintype "bidirectional"))
    )
    (net (code "181") (name "RX") (class "Default")
      (node (ref "U7") (pin "27") (pinfunction "PA8_27") (pintype "bidirectional"))
    )
    (net (code "182") (name "SCLK") (class "Default")
      (node (ref "SCLK") (pin "2") (pinfunction "2_2") (pintype "passive"))
      (node (ref "SCLK2") (pin "2") (pinfunction "2_2") (pintype "passive"))
      (node (ref "SCLK3") (pin "2") (pinfunction "2_2") (pintype "passive"))
      (node (ref "SCLK4") (pin "1") (pinfunction "1_1") (pintype "passive"))
      (node (ref "U7") (pin "110") (pinfunction "PA27_110") (pintype "bidirectional"))
    )
    (net (code "183") (name "S_BCLK") (class "Default")
      (node (ref "U7") (pin "90") (pinfunction "PB19_90") (pintype "bidirectional"))
    )
    (net (code "184") (name "S_WCLK") (class "Default")
      (node (ref "U7") (pin "88") (pinfunction "PB17_88") (pintype "bidirectional"))
    )
    (net (code "185") (name "TCK") (class "Default")
      (node (ref "JTAG") (pin "4") (pinfunction "4_4") (pintype "bidirectional"))
      (node (ref "R14") (pin "1") (pinfunction "1_1") (pintype "passive"))
      (node (ref "U7") (pin "28") (pinfunction "PB28_28") (pintype "bidirectional"))
    )
    (net (code "186") (name "TDI") (class "Default")
      (node (ref "JTAG") (pin "8") (pinfunction "8_8") (pintype "bidirectional"))
      (node (ref "R45") (pin "1") (pinfunction "1_1") (pintype "passive"))
      (node (ref "U7") (pin "29") (pinfunction "PB29_29") (pintype "bidirectional"))
    )
    (net (code "187") (name "TDO") (class "Default")
      (node (ref "JTAG") (pin "6") (pinfunction "6_6") (pintype "bidirectional"))
      (node (ref "U7") (pin "30") (pinfunction "PB30_30") (pintype "bidirectional"))
    )
    (net (code "188") (name "TMS") (class "Default")
      (node (ref "JTAG") (pin "2") (pinfunction "2_2") (pintype "bidirectional"))
      (node (ref "R11") (pin "1") (pinfunction "1_1") (pintype "passive"))
      (node (ref "U7") (pin "31") (pinfunction "PB31_31") (pintype "bidirectional"))
    )
    (net (code "189") (name "TX") (class "Default")
      (node (ref "U7") (pin "2") (pinfunction "PA9_2") (pintype "bidirectional"))
    )
    (net (code "190") (name "USBOTGID") (class "Default")
      (node (ref "U7") (pin "129") (pinfunction "PB11_129") (pintype "bidirectional"))
      (node (ref "USB2") (pin "4") (pinfunction "ID_4") (pintype "bidirectional"))
    )
    (net (code "191") (name "USB_SENSE") (class "Default")
      (node (ref "U7") (pin "19") (pinfunction "PD6_19") (pintype "bidirectional"))
      (node (ref "USB_SENSE") (pin "2") (pinfunction "2_2") (pintype "passive"))
    )
    (net (code "192") (name "WCLK") (class "Default")
      (node (ref "U3") (pin "3") (pinfunction "WCLK_3") (pintype "bidirectional"))
      (node (ref "WCLK") (pin "2") (pinfunction "2_2") (pintype "passive"))
      (node (ref "WCLK2") (pin "1") (pinfunction "1_1") (pintype "passive"))
    )
    (net (code "193") (name "X_BCLK") (class "Default")
      (node (ref "BCLK") (pin "1") (pinfunction "1_1") (pintype "passive"))
      (node (ref "L6") (pin "1") (pinfunction "1_1") (pintype "passive"))
    )
    (net (code "194") (name "X_CS_CC8531") (class "Default")
      (node (ref "CC_DEBUG") (pin "5") (pinfunction "5_5") (pintype "bidirectional"))
      (node (ref "CS_CC8531") (pin "1") (pinfunction "1_1") (pintype "passive"))
      (node (ref "U1") (pin "3") (pinfunction "CSN_3") (pintype "bidirectional"))
    )
    (net (code "195") (name "X_DIN") (class "Default")
      (node (ref "DIN") (pin "1") (pinfunction "1_1") (pintype "passive"))
      (node (ref "L13") (pin "1") (pinfunction "1_1") (pintype "passive"))
    )
    (net (code "196") (name "X_DOUT") (class "Default")
      (node (ref "DOUT") (pin "1") (pinfunction "1_1") (pintype "passive"))
      (node (ref "L11") (pin "1") (pinfunction "1_1") (pintype "passive"))
    )
    (net (code "197") (name "X_MCLK") (class "Default")
      (node (ref "L5") (pin "1") (pinfunction "1_1") (pintype "passive"))
      (node (ref "MCLK") (pin "1") (pinfunction "1_1") (pintype "passive"))
    )
    (net (code "198") (name "X_MISO") (class "Default")
      (node (ref "CC_DEBUG") (pin "10") (pinfunction "10_10") (pintype "bidirectional"))
      (node (ref "MISO") (pin "1") (pinfunction "1_1") (pintype "passive"))
      (node (ref "U1") (pin "6") (pinfunction "MISO_6") (pintype "bidirectional"))
    )
    (net (code "199") (name "X_MOSI") (class "Default")
      (node (ref "CC_DEBUG") (pin "8") (pinfunction "8_8") (pintype "bidirectional"))
      (node (ref "MOSI") (pin "1") (pinfunction "1_1") (pintype "passive"))
      (node (ref "U1") (pin "5") (pinfunction "MOSI_5") (pintype "bidirectional"))
    )
    (net (code "200") (name "X_RESET_CC8531") (class "Default")
      (node (ref "CC_DEBUG") (pin "7") (pinfunction "7_7") (pintype "bidirectional"))
      (node (ref "L4") (pin "2") (pinfunction "2_2") (pintype "passive"))
      (node (ref "RESET_CC8531") (pin "1") (pinfunction "1_1") (pintype "passive"))
    )
    (net (code "201") (name "X_SCLK") (class "Default")
      (node (ref "CC_DEBUG") (pin "6") (pinfunction "6_6") (pintype "bidirectional"))
      (node (ref "SCLK") (pin "1") (pinfunction "1_1") (pintype "passive"))
      (node (ref "U1") (pin "4") (pinfunction "SCLK_4") (pintype "bidirectional"))
    )
    (net (code "202") (name "X_USB_SENSE") (class "Default")
      (node (ref "R7") (pin "1") (pinfunction "1_1") (pintype "passive"))
      (node (ref "U1") (pin "19") (pinfunction "AD2/GIO9_19") (pintype "bidirectional"))
      (node (ref "USB_SENSE") (pin "1") (pinfunction "1_1") (pintype "passive"))
    )
    (net (code "203") (name "X_WCLK") (class "Default")
      (node (ref "L9") (pin "1") (pinfunction "1_1") (pintype "passive"))
      (node (ref "WCLK") (pin "1") (pinfunction "1_1") (pintype "passive"))
    )
    (net (code "204") (name "unconnected-(CC_DEBUG-Pad3)") (class "Default")
      (node (ref "CC_DEBUG") (pin "3") (pinfunction "3_3") (pintype "bidirectional"))
    )
    (net (code "205") (name "unconnected-(CC_DEBUG-Pad4)") (class "Default")
      (node (ref "CC_DEBUG") (pin "4") (pinfunction "4_4") (pintype "bidirectional"))
    )
    (net (code "206") (name "unconnected-(ERASE-Pad2)") (class "Default")
      (node (ref "ERASE") (pin "2") (pinfunction "2_2") (pintype "bidirectional"))
    )
    (net (code "207") (name "unconnected-(ERASE-Pad4)") (class "Default")
      (node (ref "ERASE") (pin "4") (pinfunction "4_4") (pintype "bidirectional"))
    )
    (net (code "208") (name "unconnected-(JTAG-Pad7)") (class "Default")
      (node (ref "JTAG") (pin "7") (pinfunction "7_7") (pintype "bidirectional"))
    )
    (net (code "209") (name "unconnected-(LINE_IN-R_SW-Pad2)") (class "Default")
      (node (ref "LINE_IN") (pin "2") (pinfunction "R_SW_2") (pintype "bidirectional"))
    )
    (net (code "210") (name "unconnected-(PHONE_OUT-R_SW-Pad2)") (class "Default")
      (node (ref "PHONE_OUT") (pin "2") (pinfunction "R_SW_2") (pintype "bidirectional"))
    )
    (net (code "211") (name "unconnected-(RESET-Pad2)") (class "Default")
      (node (ref "RESET") (pin "2") (pinfunction "2_2") (pintype "bidirectional"))
    )
    (net (code "212") (name "unconnected-(RESET-Pad4)") (class "Default")
      (node (ref "RESET") (pin "4") (pinfunction "4_4") (pintype "bidirectional"))
    )
    (net (code "213") (name "unconnected-(U1-SCL{slash}GIO10-Pad32)") (class "Default")
      (node (ref "U1") (pin "32") (pinfunction "SCL/GIO10_32") (pintype "bidirectional"))
    )
    (net (code "214") (name "unconnected-(U1-SDA{slash}GIO11-Pad33)") (class "Default")
      (node (ref "U1") (pin "33") (pinfunction "SDA/GIO11_33") (pintype "bidirectional"))
    )
    (net (code "215") (name "unconnected-(U2-RXTX-Pad3)") (class "Default")
      (node (ref "U2") (pin "3") (pinfunction "RXTX_3") (pintype "bidirectional"))
    )
    (net (code "216") (name "unconnected-(U3-GPIO{slash}MFP5-Pad32)") (class "Default")
      (node (ref "U3") (pin "32") (pinfunction "GPIO/MFP5_32") (pintype "bidirectional"))
    )
    (net (code "217") (name "unconnected-(U3-IN2_L-Pad15)") (class "Default")
      (node (ref "U3") (pin "15") (pinfunction "IN2_L_15") (pintype "bidirectional"))
    )
    (net (code "218") (name "unconnected-(U3-IN2_R-Pad16)") (class "Default")
      (node (ref "U3") (pin "16") (pinfunction "IN2_R_16") (pintype "bidirectional"))
    )
    (net (code "219") (name "unconnected-(U3-IN3_L-Pad20)") (class "Default")
      (node (ref "U3") (pin "20") (pinfunction "IN3_L_20") (pintype "bidirectional"))
    )
    (net (code "220") (name "unconnected-(U3-IN3_R-Pad21)") (class "Default")
      (node (ref "U3") (pin "21") (pinfunction "IN3_R_21") (pintype "bidirectional"))
    )
    (net (code "221") (name "unconnected-(U3-MICBIAS-Pad19)") (class "Default")
      (node (ref "U3") (pin "19") (pinfunction "MICBIAS_19") (pintype "bidirectional"))
    )
    (net (code "222") (name "unconnected-(U7A-PA0-Pad23)") (class "Default")
      (node (ref "U7") (pin "23") (pinfunction "PA0_23") (pintype "bidirectional"))
    )
    (net (code "223") (name "unconnected-(U7A-PA1-Pad24)") (class "Default")
      (node (ref "U7") (pin "24") (pinfunction "PA1_24") (pintype "bidirectional"))
    )
    (net (code "224") (name "unconnected-(U7A-PA3-Pad84)") (class "Default")
      (node (ref "U7") (pin "84") (pinfunction "PA3_84") (pintype "bidirectional"))
    )
    (net (code "225") (name "unconnected-(U7A-PA4-Pad83)") (class "Default")
      (node (ref "U7") (pin "83") (pinfunction "PA4_83") (pintype "bidirectional"))
    )
    (net (code "226") (name "unconnected-(U7A-PA5-Pad25)") (class "Default")
      (node (ref "U7") (pin "25") (pinfunction "PA5_25") (pintype "bidirectional"))
    )
    (net (code "227") (name "unconnected-(U7A-PA6-Pad82)") (class "Default")
      (node (ref "U7") (pin "82") (pinfunction "PA6_82") (pintype "bidirectional"))
    )
    (net (code "228") (name "unconnected-(U7A-PA10-Pad3)") (class "Default")
      (node (ref "U7") (pin "3") (pinfunction "PA10_3") (pintype "bidirectional"))
    )
    (net (code "229") (name "unconnected-(U7A-PA11-Pad4)") (class "Default")
      (node (ref "U7") (pin "4") (pinfunction "PA11_4") (pintype "bidirectional"))
    )
    (net (code "230") (name "unconnected-(U7A-PA12-Pad5)") (class "Default")
      (node (ref "U7") (pin "5") (pinfunction "PA12_5") (pintype "bidirectional"))
    )
    (net (code "231") (name "unconnected-(U7A-PA13-Pad6)") (class "Default")
      (node (ref "U7") (pin "6") (pinfunction "PA13_6") (pintype "bidirectional"))
    )
    (net (code "232") (name "unconnected-(U7A-PA17-Pad9)") (class "Default")
      (node (ref "U7") (pin "9") (pinfunction "PA17_9") (pintype "bidirectional"))
    )
    (net (code "233") (name "unconnected-(U7A-PA18-Pad70)") (class "Default")
      (node (ref "U7") (pin "70") (pinfunction "PA18_70") (pintype "bidirectional"))
    )
    (net (code "234") (name "unconnected-(U7A-PA21-Pad107)") (class "Default")
      (node (ref "U7") (pin "107") (pinfunction "PA21_107") (pintype "bidirectional"))
    )
    (net (code "235") (name "unconnected-(U7A-PA22-Pad81)") (class "Default")
      (node (ref "U7") (pin "81") (pinfunction "PA22_81") (pintype "bidirectional"))
    )
    (net (code "236") (name "unconnected-(U7A-PA23-Pad80)") (class "Default")
      (node (ref "U7") (pin "80") (pinfunction "PA23_80") (pintype "bidirectional"))
    )
    (net (code "237") (name "unconnected-(U7A-PA24-Pad79)") (class "Default")
      (node (ref "U7") (pin "79") (pinfunction "PA24_79") (pintype "bidirectional"))
    )
    (net (code "238") (name "unconnected-(U7A-PA28-Pad111)") (class "Default")
      (node (ref "U7") (pin "111") (pinfunction "PA28_111") (pintype "bidirectional"))
    )
    (net (code "239") (name "unconnected-(U7A-PA29-Pad112)") (class "Default")
      (node (ref "U7") (pin "112") (pinfunction "PA29_112") (pintype "bidirectional"))
    )
    (net (code "240") (name "unconnected-(U7B-PB0-Pad113)") (class "Default")
      (node (ref "U7") (pin "113") (pinfunction "PB0_113") (pintype "bidirectional"))
    )
    (net (code "241") (name "unconnected-(U7B-PB1-Pad114)") (class "Default")
      (node (ref "U7") (pin "114") (pinfunction "PB1_114") (pintype "bidirectional"))
    )
    (net (code "242") (name "unconnected-(U7B-PB2-Pad115)") (class "Default")
      (node (ref "U7") (pin "115") (pinfunction "PB2_115") (pintype "bidirectional"))
    )
    (net (code "243") (name "unconnected-(U7B-PB3-Pad118)") (class "Default")
      (node (ref "U7") (pin "118") (pinfunction "PB3_118") (pintype "bidirectional"))
    )
    (net (code "244") (name "unconnected-(U7B-PB4-Pad119)") (class "Default")
      (node (ref "U7") (pin "119") (pinfunction "PB4_119") (pintype "bidirectional"))
    )
    (net (code "245") (name "unconnected-(U7B-PB5-Pad120)") (class "Default")
      (node (ref "U7") (pin "120") (pinfunction "PB5_120") (pintype "bidirectional"))
    )
    (net (code "246") (name "unconnected-(U7B-PB6-Pad121)") (class "Default")
      (node (ref "U7") (pin "121") (pinfunction "PB6_121") (pintype "bidirectional"))
    )
    (net (code "247") (name "unconnected-(U7B-PB7-Pad122)") (class "Default")
      (node (ref "U7") (pin "122") (pinfunction "PB7_122") (pintype "bidirectional"))
    )
    (net (code "248") (name "unconnected-(U7B-PB8-Pad123)") (class "Default")
      (node (ref "U7") (pin "123") (pinfunction "PB8_123") (pintype "bidirectional"))
    )
    (net (code "249") (name "unconnected-(U7B-PB9-Pad127)") (class "Default")
      (node (ref "U7") (pin "127") (pinfunction "PB9_127") (pintype "bidirectional"))
    )
    (net (code "250") (name "unconnected-(U7B-PB10-Pad128)") (class "Default")
      (node (ref "U7") (pin "128") (pinfunction "PB10_128") (pintype "bidirectional"))
    )
    (net (code "251") (name "unconnected-(U7B-PB12-Pad86)") (class "Default")
      (node (ref "U7") (pin "86") (pinfunction "PB12_86") (pintype "bidirectional"))
    )
    (net (code "252") (name "unconnected-(U7B-PB13-Pad87)") (class "Default")
      (node (ref "U7") (pin "87") (pinfunction "PB13_87") (pintype "bidirectional"))
    )
    (net (code "253") (name "unconnected-(U7B-PB15-Pad76)") (class "Default")
      (node (ref "U7") (pin "76") (pinfunction "PB15_76") (pintype "bidirectional"))
    )
    (net (code "254") (name "unconnected-(U7B-PB16-Pad77)") (class "Default")
      (node (ref "U7") (pin "77") (pinfunction "PB16_77") (pintype "bidirectional"))
    )
    (net (code "255") (name "unconnected-(U7B-PB20-Pad91)") (class "Default")
      (node (ref "U7") (pin "91") (pinfunction "PB20_91") (pintype "bidirectional"))
    )
    (net (code "256") (name "unconnected-(U7B-PB21-Pad92)") (class "Default")
      (node (ref "U7") (pin "92") (pinfunction "PB21_92") (pintype "bidirectional"))
    )
    (net (code "257") (name "unconnected-(U7B-PB22-Pad141)") (class "Default")
      (node (ref "U7") (pin "141") (pinfunction "PB22_141") (pintype "bidirectional"))
    )
    (net (code "258") (name "unconnected-(U7B-PB23-Pad142)") (class "Default")
      (node (ref "U7") (pin "142") (pinfunction "PB23_142") (pintype "bidirectional"))
    )
    (net (code "259") (name "unconnected-(U7B-PB24-Pad143)") (class "Default")
      (node (ref "U7") (pin "143") (pinfunction "PB24_143") (pintype "bidirectional"))
    )
    (net (code "260") (name "unconnected-(U7B-PB25-Pad144)") (class "Default")
      (node (ref "U7") (pin "144") (pinfunction "PB25_144") (pintype "bidirectional"))
    )
    (net (code "261") (name "unconnected-(U7B-PB26-Pad1)") (class "Default")
      (node (ref "U7") (pin "1") (pinfunction "PB26_1") (pintype "bidirectional"))
    )
    (net (code "262") (name "unconnected-(U7C-PC1-Pad55)") (class "Default")
      (node (ref "U7") (pin "55") (pinfunction "PC1_55") (pintype "bidirectional"))
    )
    (net (code "263") (name "unconnected-(U7C-PC2-Pad59)") (class "Default")
      (node (ref "U7") (pin "59") (pinfunction "PC2_59") (pintype "bidirectional"))
    )
    (net (code "264") (name "unconnected-(U7C-PC3-Pad60)") (class "Default")
      (node (ref "U7") (pin "60") (pinfunction "PC3_60") (pintype "bidirectional"))
    )
    (net (code "265") (name "unconnected-(U7C-PC4-Pad116)") (class "Default")
      (node (ref "U7") (pin "116") (pinfunction "PC4_116") (pintype "bidirectional"))
    )
    (net (code "266") (name "unconnected-(U7C-PC5-Pad63)") (class "Default")
      (node (ref "U7") (pin "63") (pinfunction "PC5_63") (pintype "bidirectional"))
    )
    (net (code "267") (name "unconnected-(U7C-PC6-Pad64)") (class "Default")
      (node (ref "U7") (pin "64") (pinfunction "PC6_64") (pintype "bidirectional"))
    )
    (net (code "268") (name "unconnected-(U7C-PC7-Pad65)") (class "Default")
      (node (ref "U7") (pin "65") (pinfunction "PC7_65") (pintype "bidirectional"))
    )
    (net (code "269") (name "unconnected-(U7C-PC10-Pad117)") (class "Default")
      (node (ref "U7") (pin "117") (pinfunction "PC10_117") (pintype "bidirectional"))
    )
    (net (code "270") (name "unconnected-(U7C-PC11-Pad93)") (class "Default")
      (node (ref "U7") (pin "93") (pinfunction "PC11_93") (pintype "bidirectional"))
    )
    (net (code "271") (name "unconnected-(U7C-PC12-Pad94)") (class "Default")
      (node (ref "U7") (pin "94") (pinfunction "PC12_94") (pintype "bidirectional"))
    )
    (net (code "272") (name "unconnected-(U7C-PC13-Pad95)") (class "Default")
      (node (ref "U7") (pin "95") (pinfunction "PC13_95") (pintype "bidirectional"))
    )
    (net (code "273") (name "unconnected-(U7C-PC14-Pad96)") (class "Default")
      (node (ref "U7") (pin "96") (pinfunction "PC14_96") (pintype "bidirectional"))
    )
    (net (code "274") (name "unconnected-(U7C-PC15-Pad97)") (class "Default")
      (node (ref "U7") (pin "97") (pinfunction "PC15_97") (pintype "bidirectional"))
    )
    (net (code "275") (name "unconnected-(U7C-PC16-Pad98)") (class "Default")
      (node (ref "U7") (pin "98") (pinfunction "PC16_98") (pintype "bidirectional"))
    )
    (net (code "276") (name "unconnected-(U7C-PC17-Pad99)") (class "Default")
      (node (ref "U7") (pin "99") (pinfunction "PC17_99") (pintype "bidirectional"))
    )
    (net (code "277") (name "unconnected-(U7C-PC18-Pad100)") (class "Default")
      (node (ref "U7") (pin "100") (pinfunction "PC18_100") (pintype "bidirectional"))
    )
    (net (code "278") (name "unconnected-(U7C-PC20-Pad131)") (class "Default")
      (node (ref "U7") (pin "131") (pinfunction "PC20_131") (pintype "bidirectional"))
    )
    (net (code "279") (name "unconnected-(U7C-PC26-Pad137)") (class "Default")
      (node (ref "U7") (pin "137") (pinfunction "PC26_137") (pintype "bidirectional"))
    )
    (net (code "280") (name "unconnected-(U7C-PC27-Pad138)") (class "Default")
      (node (ref "U7") (pin "138") (pinfunction "PC27_138") (pintype "bidirectional"))
    )
    (net (code "281") (name "unconnected-(U7C-PC29-Pad102)") (class "Default")
      (node (ref "U7") (pin "102") (pinfunction "PC29_102") (pintype "bidirectional"))
    )
    (net (code "282") (name "unconnected-(U7C-PC30-Pad103)") (class "Default")
      (node (ref "U7") (pin "103") (pinfunction "PC30_103") (pintype "bidirectional"))
    )
    (net (code "283") (name "unconnected-(U7D-PD0-Pad13)") (class "Default")
      (node (ref "U7") (pin "13") (pinfunction "PD0_13") (pintype "bidirectional"))
    )
    (net (code "284") (name "unconnected-(U7D-PD1-Pad14)") (class "Default")
      (node (ref "U7") (pin "14") (pinfunction "PD1_14") (pintype "bidirectional"))
    )
    (net (code "285") (name "unconnected-(U7D-PD4-Pad17)") (class "Default")
      (node (ref "U7") (pin "17") (pinfunction "PD4_17") (pintype "bidirectional"))
    )
    (net (code "286") (name "unconnected-(U7D-PD5-Pad18)") (class "Default")
      (node (ref "U7") (pin "18") (pinfunction "PD5_18") (pintype "bidirectional"))
    )
    (net (code "287") (name "unconnected-(U7F-NRST-Pad69)") (class "Default")
      (node (ref "U7") (pin "69") (pinfunction "NRST_69") (pintype "bidirectional"))
    )
    (net (code "288") (name "unconnected-(U7F-SHDN-Pad50)") (class "Default")
      (node (ref "U7") (pin "50") (pinfunction "SHDN_50") (pintype "bidirectional"))
    )
    (net (code "289") (name "unconnected-(U7F-TST-Pad51)") (class "Default")
      (node (ref "U7") (pin "51") (pinfunction "TST_51") (pintype "bidirectional"))
    )
    (net (code "290") (name "unconnected-(U7F-XIN32-Pad48)") (class "Default")
      (node (ref "U7") (pin "48") (pinfunction "XIN32_48") (pintype "bidirectional"))
    )
    (net (code "291") (name "unconnected-(U7F-XOUT32-Pad49)") (class "Default")
      (node (ref "U7") (pin "49") (pinfunction "XOUT32_49") (pintype "bidirectional"))
    )
    (net (code "292") (name "unconnected-(U8-SNS0-Pad32)") (class "Default")
      (node (ref "U8") (pin "32") (pinfunction "SNS0_32") (pintype "bidirectional"))
    )
    (net (code "293") (name "unconnected-(U8-SNS0K-Pad1)") (class "Default")
      (node (ref "U8") (pin "1") (pinfunction "SNS0K_1") (pintype "bidirectional"))
    )
    (net (code "294") (name "unconnected-(U8-SNS1-Pad2)") (class "Default")
      (node (ref "U8") (pin "2") (pinfunction "SNS1_2") (pintype "bidirectional"))
    )
    (net (code "295") (name "unconnected-(U8-SNS1K-Pad3)") (class "Default")
      (node (ref "U8") (pin "3") (pinfunction "SNS1K_3") (pintype "bidirectional"))
    )
    (net (code "296") (name "unconnected-(U8-SNS2-Pad7)") (class "Default")
      (node (ref "U8") (pin "7") (pinfunction "SNS2_7") (pintype "bidirectional"))
    )
    (net (code "297") (name "unconnected-(U8-SNS2K-Pad6)") (class "Default")
      (node (ref "U8") (pin "6") (pinfunction "SNS2K_6") (pintype "bidirectional"))
    )
    (net (code "298") (name "unconnected-(USB1-ID-Pad4)") (class "Default")
      (node (ref "USB1") (pin "4") (pinfunction "ID_4") (pintype "bidirectional"))
    )
  )
)
